# Arduhub_plane.net
KiCad netlist of a schematic drawn in EAGLE
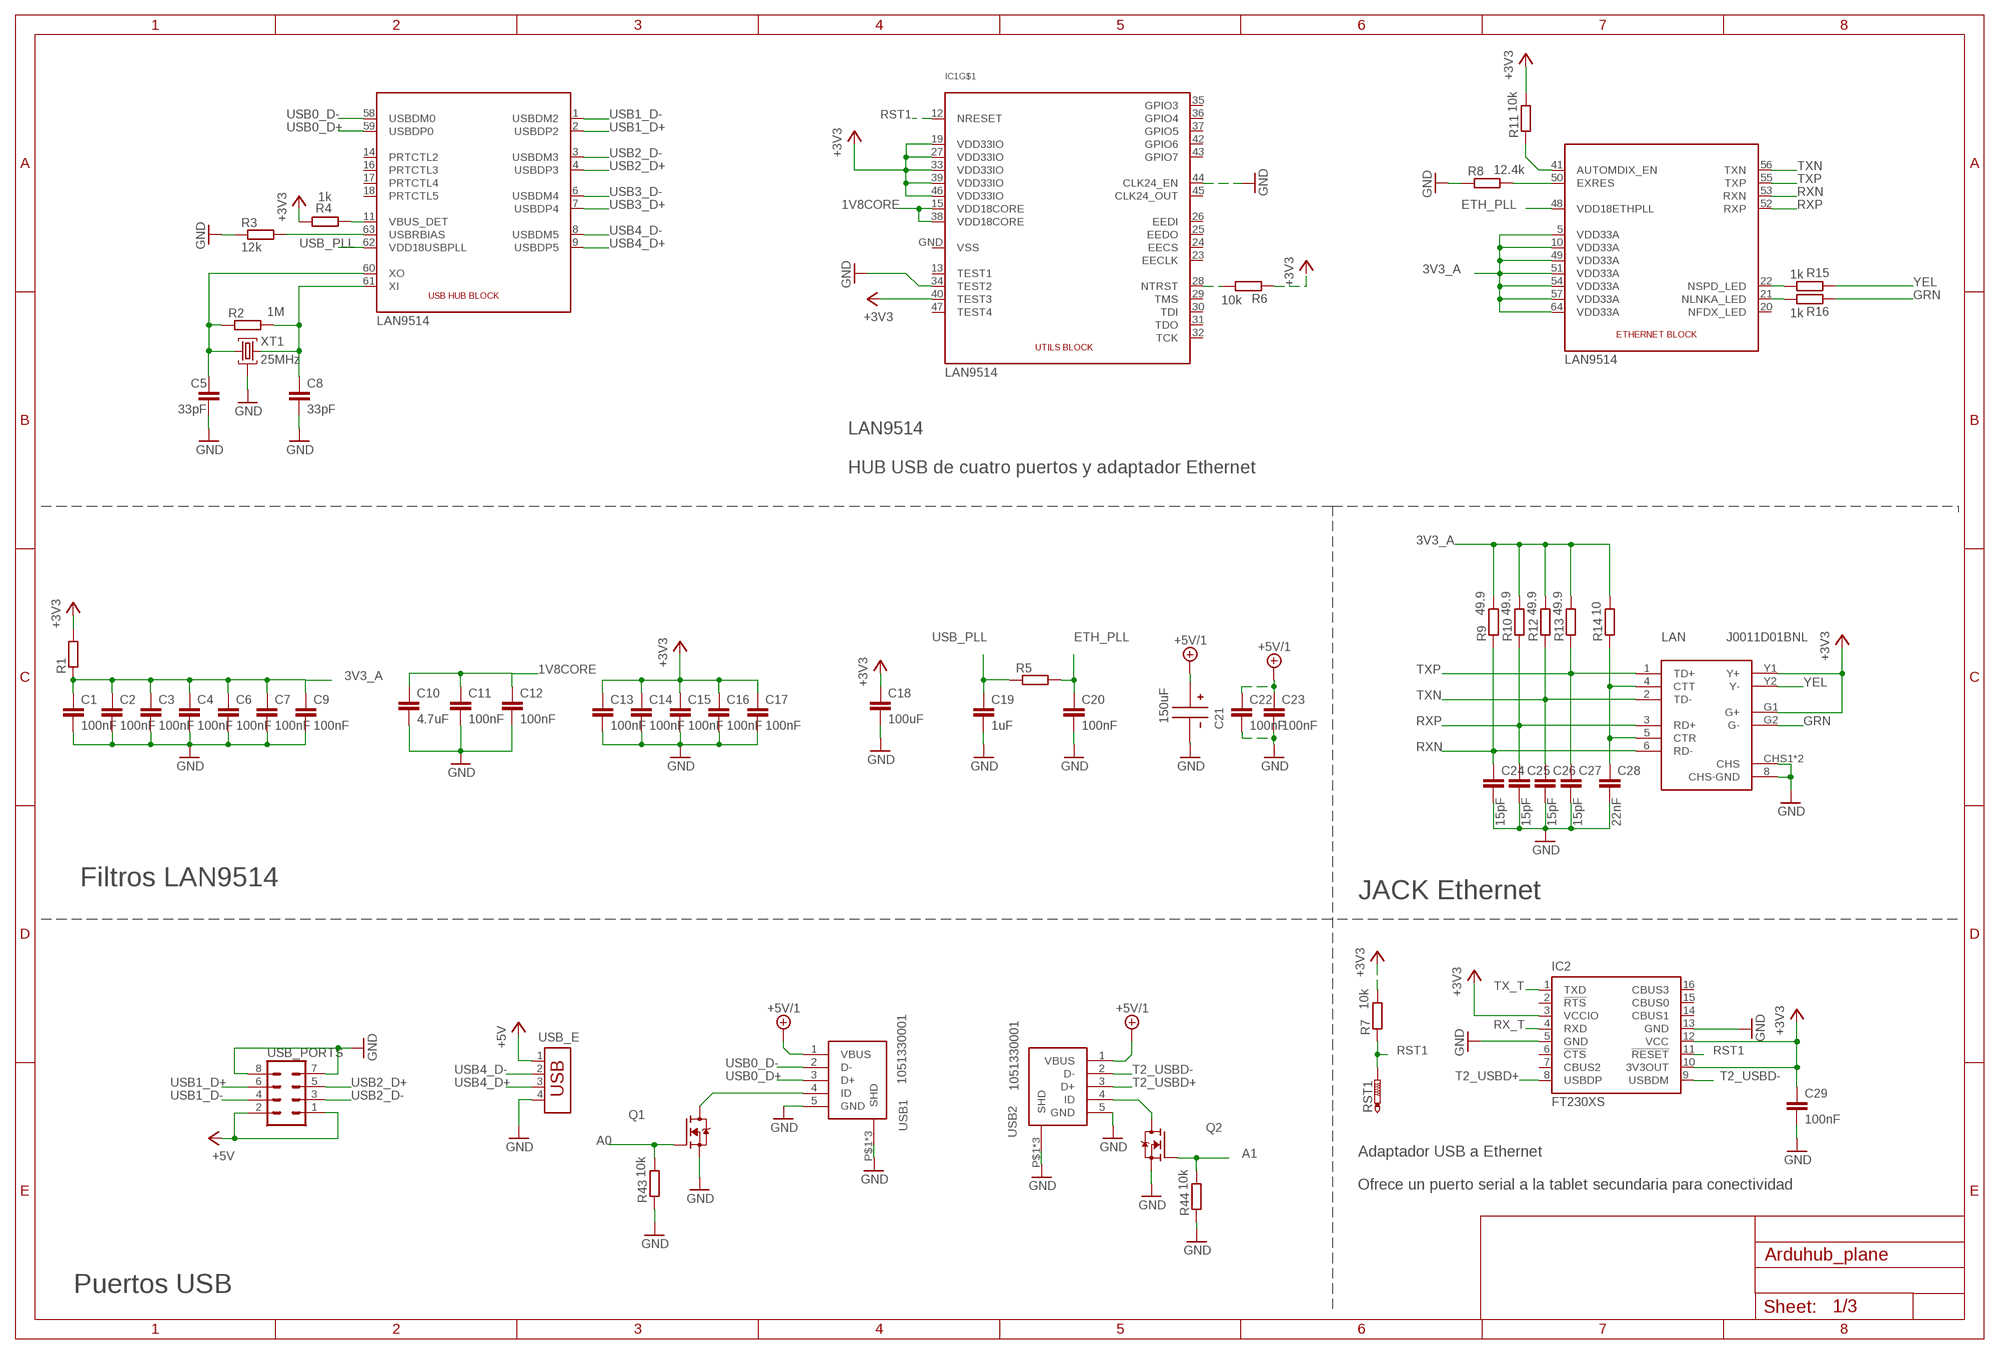
[diagram p0: schematic, sheet 1]
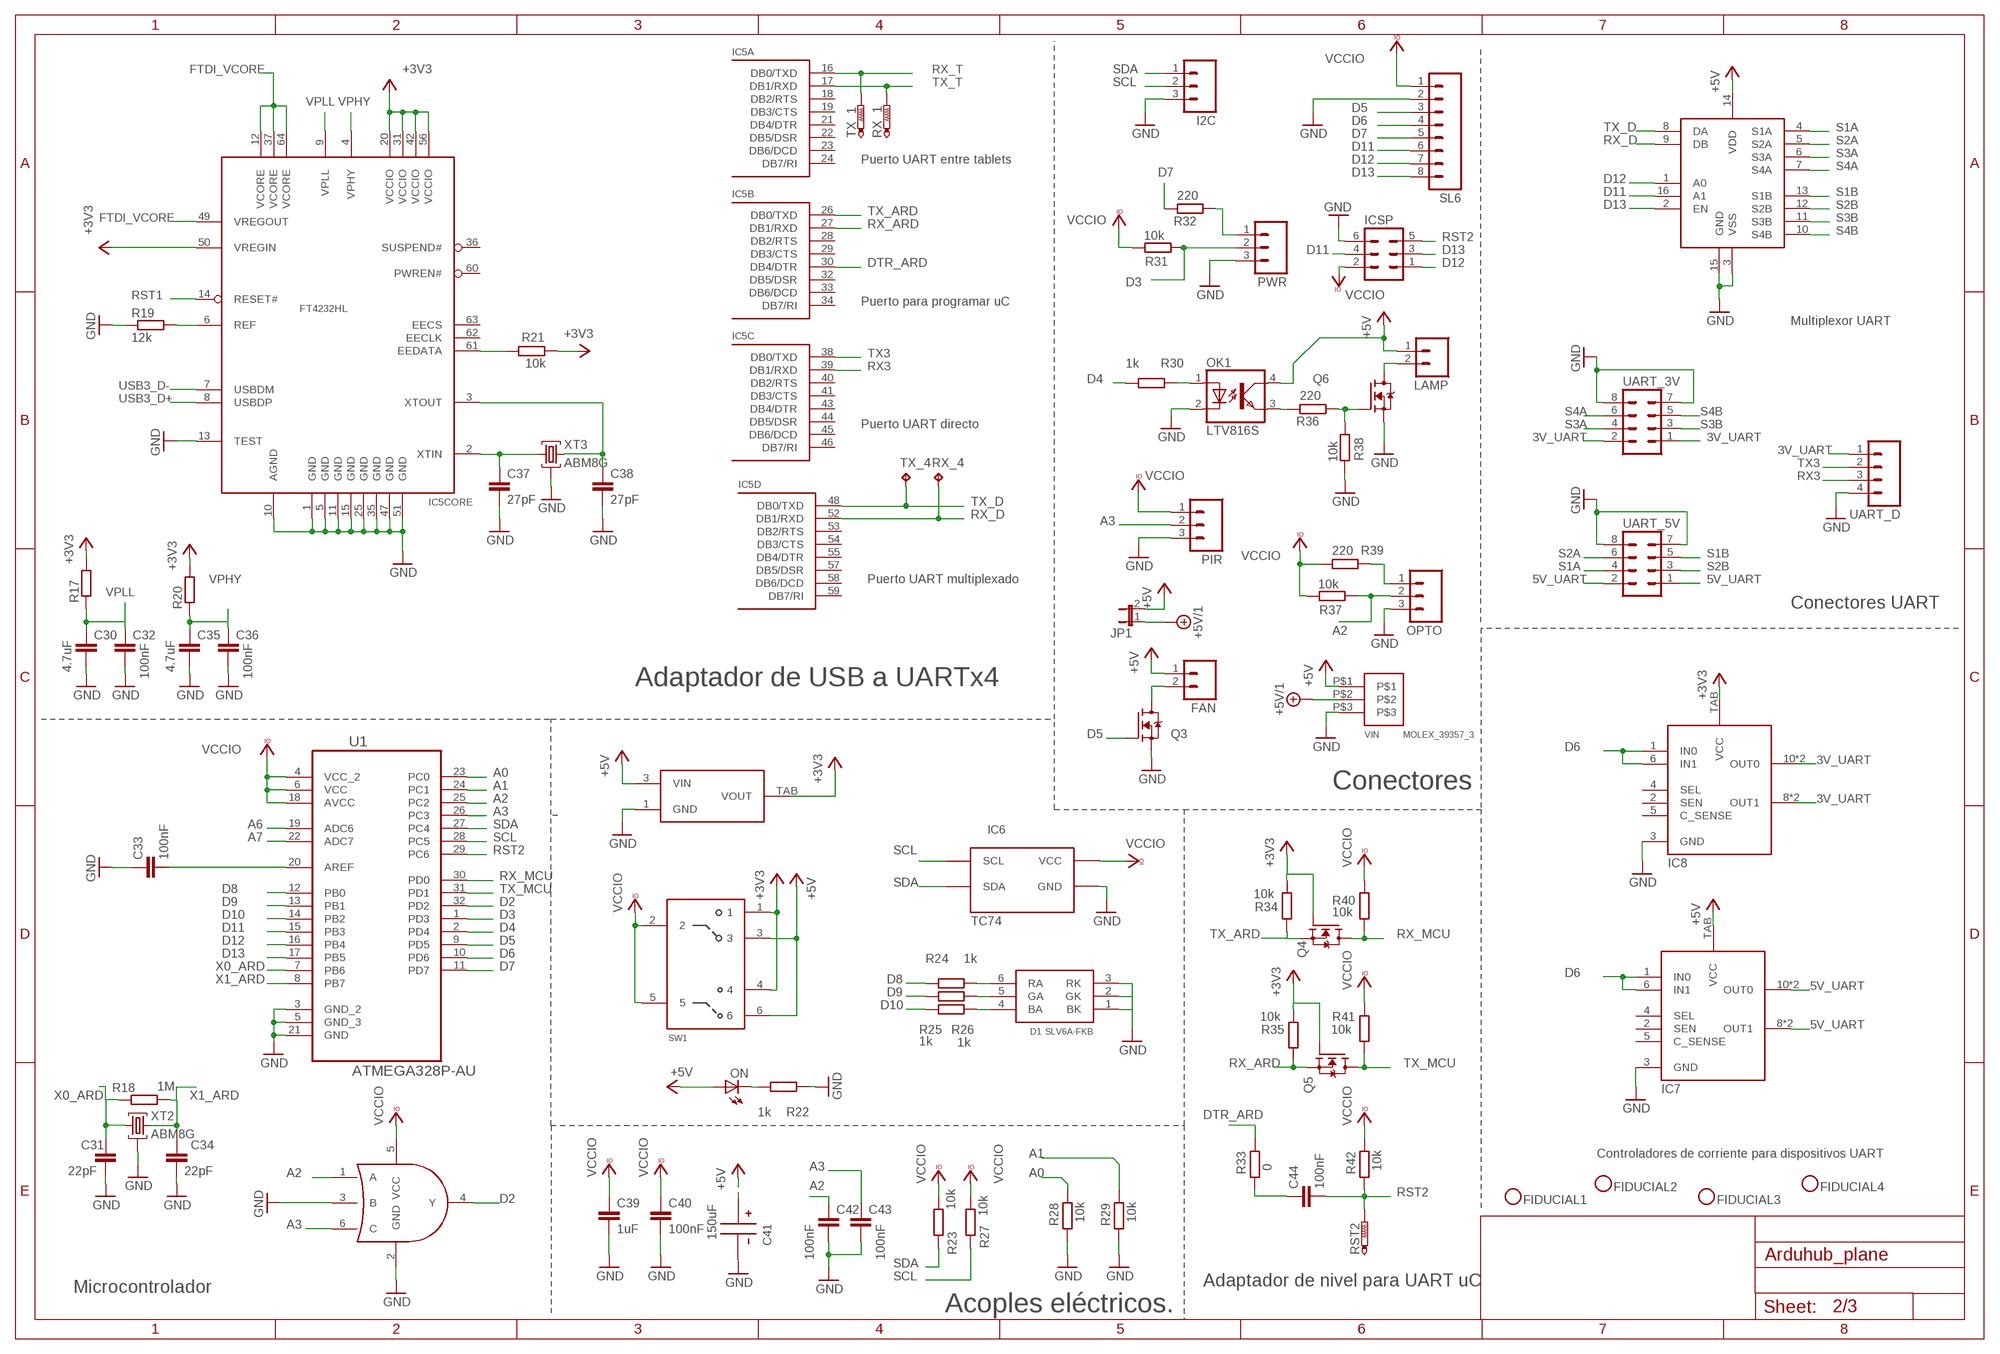
[diagram p1: schematic, sheet 2]
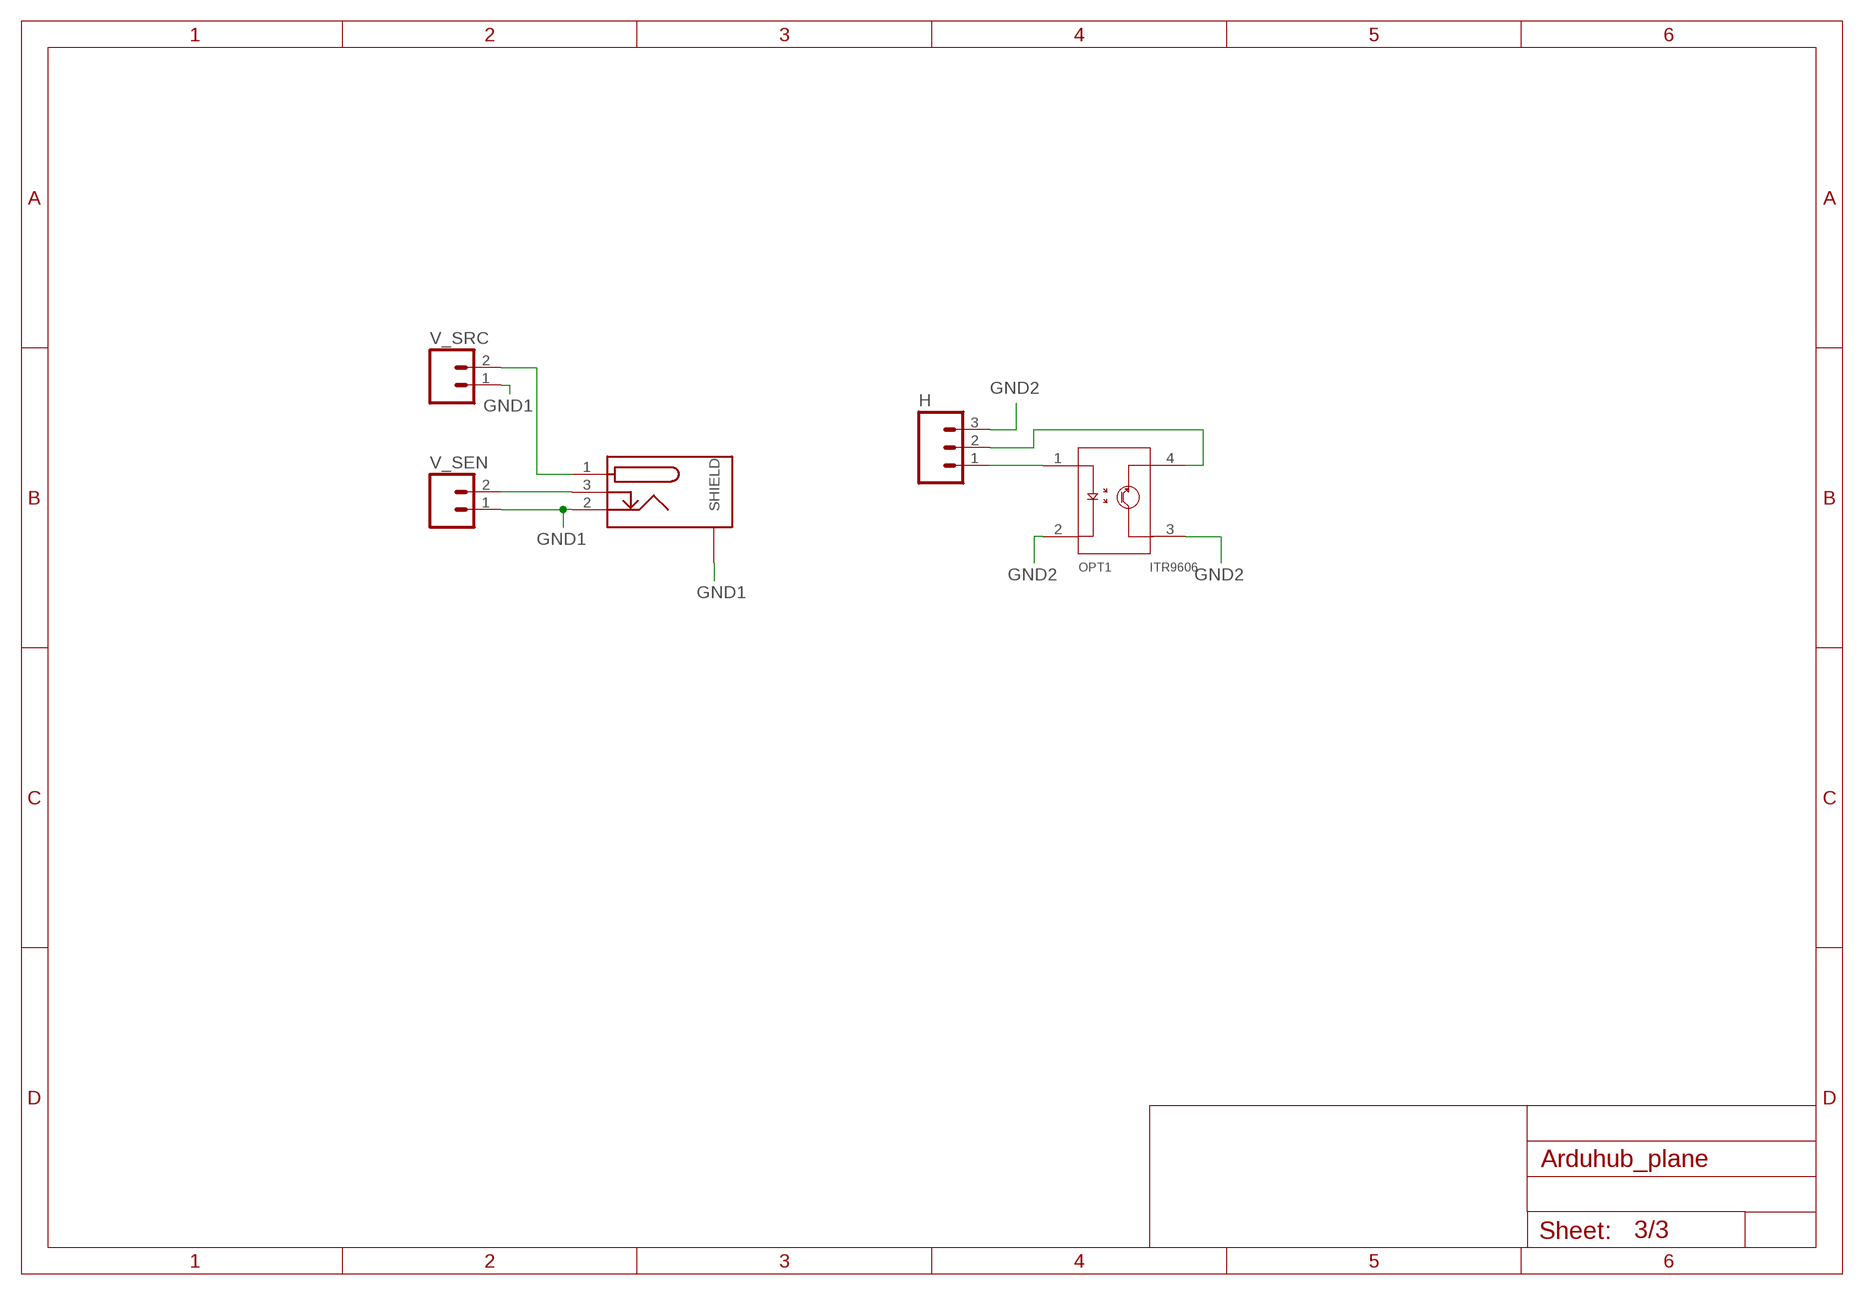
[diagram p2: schematic, sheet 3]

(export (version "E")
  (design (tool "Eeschema 10.0.6"))
  (components
    (comp (ref "C30")
      (value "4.7uF")
      (footprint "eagle-import:C0402")
      (libsource (lib "eagle-import") (part "C-EUC0402"))
    )
    (comp (ref "C31")
      (value "22pF")
      (footprint "eagle-import:C0402")
      (libsource (lib "eagle-import") (part "C-EUC0402"))
    )
    (comp (ref "C32")
      (value "100nF")
      (footprint "eagle-import:C0402")
      (libsource (lib "eagle-import") (part "C-EUC0402"))
    )
    (comp (ref "C33")
      (value "100nF")
      (footprint "eagle-import:C0402")
      (libsource (lib "eagle-import") (part "C-EUC0402"))
    )
    (comp (ref "C34")
      (value "22pF")
      (footprint "eagle-import:C0402")
      (libsource (lib "eagle-import") (part "C-EUC0402"))
    )
    (comp (ref "C35")
      (value "4.7uF")
      (footprint "eagle-import:C0402")
      (libsource (lib "eagle-import") (part "C-EUC0402"))
    )
    (comp (ref "C36")
      (value "100nF")
      (footprint "eagle-import:C0402")
      (libsource (lib "eagle-import") (part "C-EUC0402"))
    )
    (comp (ref "C37")
      (value "27pF")
      (footprint "eagle-import:C0402")
      (libsource (lib "eagle-import") (part "C-EUC0402"))
    )
    (comp (ref "C38")
      (value "27pF")
      (footprint "eagle-import:C0402")
      (libsource (lib "eagle-import") (part "C-EUC0402"))
    )
    (comp (ref "C39")
      (value "1uF")
      (footprint "eagle-import:C0402")
      (libsource (lib "eagle-import") (part "C-EUC0402"))
    )
    (comp (ref "C40")
      (value "100nF")
      (footprint "eagle-import:C0402")
      (libsource (lib "eagle-import") (part "C-EUC0402"))
    )
    (comp (ref "C41")
      (value "150uF")
      (footprint "eagle-import:MVA_CAP_F55")
      (libsource (lib "eagle-import") (part "EMVE100ADA151MF55G"))
    )
    (comp (ref "C42")
      (value "100nF")
      (footprint "eagle-import:C0402")
      (libsource (lib "eagle-import") (part "C-EUC0402"))
    )
    (comp (ref "C43")
      (value "100nF")
      (footprint "eagle-import:C0402")
      (libsource (lib "eagle-import") (part "C-EUC0402"))
    )
    (comp (ref "C44")
      (value "100nF")
      (footprint "eagle-import:C0402")
      (libsource (lib "eagle-import") (part "C-EUC0402"))
    )
    (comp (ref "D1")
      (value "SLV6A-FKB")
      (footprint "eagle-import:PLCC-6")
      (libsource (lib "eagle-import") (part "SLV6A-FKB"))
    )
    (comp (ref "FAN")
      (value "M02")
      (footprint "eagle-import:02P")
      (libsource (lib "eagle-import") (part "M02"))
    )
    (comp (ref "FIDUCIAL1")
      (value "FIDU_2C")
      (footprint "eagle-import:FIDUCIAL_TEST_2C")
      (libsource (lib "eagle-import") (part "FIDU_2C"))
    )
    (comp (ref "FIDUCIAL2")
      (value "FIDU_2C")
      (footprint "eagle-import:FIDUCIAL_TEST_2C")
      (libsource (lib "eagle-import") (part "FIDU_2C"))
    )
    (comp (ref "FIDUCIAL3")
      (value "FIDU_2C")
      (footprint "eagle-import:FIDUCIAL_TEST_2C")
      (libsource (lib "eagle-import") (part "FIDU_2C"))
    )
    (comp (ref "FIDUCIAL4")
      (value "FIDU_2C")
      (footprint "eagle-import:FIDUCIAL_TEST_2C")
      (libsource (lib "eagle-import") (part "FIDU_2C"))
    )
    (comp (ref "I2C")
      (value "M03")
      (footprint "eagle-import:03P")
      (libsource (lib "eagle-import") (part "M03"))
    )
    (comp (ref "IC3")
      (value "SN74LVC1G332DBVR")
      (footprint "eagle-import:SOT-23-6")
      (libsource (lib "eagle-import") (part "SN74LVC1G332DBVR"))
    )
    (comp (ref "IC4")
      (value "AP1084D")
      (footprint "eagle-import:TO_252_3")
      (libsource (lib "eagle-import") (part "AP1084D"))
    )
    (comp (ref "IC5")
      (value "FT4232HL")
      (footprint "eagle-import:LQFP64")
      (fields (field (name "REF") "FT4232HL-REEL"))
      (libsource (lib "eagle-import") (part "FT4232HL"))
    )
    (comp (ref "IC6")
      (value "TC74")
      (footprint "eagle-import:SOT-23-5")
      (libsource (lib "eagle-import") (part "TC74"))
    )
    (comp (ref "IC7")
      (value "VND7140AJ12TR")
      (footprint "eagle-import:POWERSSO-12")
      (libsource (lib "eagle-import") (part "VND7140AJ12TR"))
    )
    (comp (ref "IC8")
      (value "VND7140AJ12TR")
      (footprint "eagle-import:POWERSSO-12")
      (libsource (lib "eagle-import") (part "VND7140AJ12TR"))
    )
    (comp (ref "IC9")
      (value "MUX509IPWR")
      (footprint "eagle-import:TSSOP-16")
      (libsource (lib "eagle-import") (part "MUX509IPWR"))
    )
    (comp (ref "ICSP")
      (value "MA03-2")
      (footprint "eagle-import:MA03-2")
      (libsource (lib "eagle-import") (part "MA03-2"))
    )
    (comp (ref "JP1")
      (value "JP1E")
      (footprint "eagle-import:JP1")
      (libsource (lib "eagle-import") (part "JP1E"))
    )
    (comp (ref "LAMP")
      (value "M02")
      (footprint "eagle-import:02P")
      (libsource (lib "eagle-import") (part "M02"))
    )
    (comp (ref "OK1")
      (value "LTV816S")
      (footprint "eagle-import:SMD4")
      (libsource (lib "eagle-import") (part "LTV816S"))
    )
    (comp (ref "ON")
      (value "LED-0603")
      (footprint "eagle-import:LED-603")
      (libsource (lib "eagle-import") (part "LED-0603"))
    )
    (comp (ref "OPTO")
      (value "M03")
      (footprint "eagle-import:03P")
      (libsource (lib "eagle-import") (part "M03"))
    )
    (comp (ref "PIR")
      (value "M03")
      (footprint "eagle-import:03P")
      (libsource (lib "eagle-import") (part "M03"))
    )
    (comp (ref "PWR")
      (value "M03")
      (footprint "eagle-import:03P")
      (libsource (lib "eagle-import") (part "M03"))
    )
    (comp (ref "Q3")
      (value "TRANSISTOR_FET_BS170-SOT-23")
      (footprint "eagle-import:SOT-23")
      (libsource (lib "eagle-import") (part "TRANSISTOR_FET_BS170-SOT-23"))
    )
    (comp (ref "Q4")
      (value "TRANSISTOR_FET_BS170-SOT-23")
      (footprint "eagle-import:SOT-23")
      (libsource (lib "eagle-import") (part "TRANSISTOR_FET_BS170-SOT-23"))
    )
    (comp (ref "Q5")
      (value "TRANSISTOR_FET_BS170-SOT-23")
      (footprint "eagle-import:SOT-23")
      (libsource (lib "eagle-import") (part "TRANSISTOR_FET_BS170-SOT-23"))
    )
    (comp (ref "Q6")
      (value "TRANSISTOR_FET_BS170-SOT-23")
      (footprint "eagle-import:SOT-23")
      (libsource (lib "eagle-import") (part "TRANSISTOR_FET_BS170-SOT-23"))
    )
    (comp (ref "R17")
      (value "R-EU_R0603")
      (footprint "eagle-import:R0603")
      (libsource (lib "eagle-import") (part "R-EU_R0603"))
    )
    (comp (ref "R18")
      (value "1M")
      (footprint "eagle-import:R0402")
      (libsource (lib "eagle-import") (part "R-EU_R0402"))
    )
    (comp (ref "R19")
      (value "12k")
      (footprint "eagle-import:R0402")
      (libsource (lib "eagle-import") (part "R-EU_R0402"))
    )
    (comp (ref "R20")
      (value "R-EU_R0603")
      (footprint "eagle-import:R0603")
      (libsource (lib "eagle-import") (part "R-EU_R0603"))
    )
    (comp (ref "R21")
      (value "10k")
      (footprint "eagle-import:R0402")
      (libsource (lib "eagle-import") (part "R-EU_R0402"))
    )
    (comp (ref "R22")
      (value "1k")
      (footprint "eagle-import:R0402")
      (libsource (lib "eagle-import") (part "R-EU_R0402"))
    )
    (comp (ref "R23")
      (value "10k")
      (footprint "eagle-import:R0402")
      (libsource (lib "eagle-import") (part "R-EU_R0402"))
    )
    (comp (ref "R24")
      (value "1k")
      (footprint "eagle-import:R0402")
      (libsource (lib "eagle-import") (part "R-EU_R0402"))
    )
    (comp (ref "R25")
      (value "1k")
      (footprint "eagle-import:R0402")
      (libsource (lib "eagle-import") (part "R-EU_R0402"))
    )
    (comp (ref "R26")
      (value "1k")
      (footprint "eagle-import:R0402")
      (libsource (lib "eagle-import") (part "R-EU_R0402"))
    )
    (comp (ref "R27")
      (value "10k")
      (footprint "eagle-import:R0402")
      (libsource (lib "eagle-import") (part "R-EU_R0402"))
    )
    (comp (ref "R28")
      (value "10k")
      (footprint "eagle-import:R0402")
      (libsource (lib "eagle-import") (part "R-EU_R0402"))
    )
    (comp (ref "R29")
      (value "10k")
      (footprint "eagle-import:R0402")
      (libsource (lib "eagle-import") (part "R-EU_R0402"))
    )
    (comp (ref "R30")
      (value "1k")
      (footprint "eagle-import:R0402")
      (libsource (lib "eagle-import") (part "R-EU_R0402"))
    )
    (comp (ref "R31")
      (value "10k")
      (footprint "eagle-import:R0402")
      (libsource (lib "eagle-import") (part "R-EU_R0402"))
    )
    (comp (ref "R32")
      (value "220")
      (footprint "eagle-import:R0402")
      (libsource (lib "eagle-import") (part "R-EU_R0402"))
    )
    (comp (ref "R33")
      (value "0")
      (footprint "eagle-import:R0402")
      (libsource (lib "eagle-import") (part "R-EU_R0402"))
    )
    (comp (ref "R34")
      (value "10k")
      (footprint "eagle-import:R0402")
      (libsource (lib "eagle-import") (part "R-EU_R0402"))
    )
    (comp (ref "R35")
      (value "10k")
      (footprint "eagle-import:R0402")
      (libsource (lib "eagle-import") (part "R-EU_R0402"))
    )
    (comp (ref "R36")
      (value "220")
      (footprint "eagle-import:R0402")
      (libsource (lib "eagle-import") (part "R-EU_R0402"))
    )
    (comp (ref "R37")
      (value "10k")
      (footprint "eagle-import:R0402")
      (libsource (lib "eagle-import") (part "R-EU_R0402"))
    )
    (comp (ref "R38")
      (value "10k")
      (footprint "eagle-import:R0402")
      (libsource (lib "eagle-import") (part "R-EU_R0402"))
    )
    (comp (ref "R39")
      (value "220")
      (footprint "eagle-import:R0402")
      (libsource (lib "eagle-import") (part "R-EU_R0402"))
    )
    (comp (ref "R40")
      (value "10k")
      (footprint "eagle-import:R0402")
      (libsource (lib "eagle-import") (part "R-EU_R0402"))
    )
    (comp (ref "R41")
      (value "10k")
      (footprint "eagle-import:R0402")
      (libsource (lib "eagle-import") (part "R-EU_R0402"))
    )
    (comp (ref "R42")
      (value "10k")
      (footprint "eagle-import:R0402")
      (libsource (lib "eagle-import") (part "R-EU_R0402"))
    )
    (comp (ref "RST2")
      (value "PTR1TP06SQ")
      (footprint "eagle-import:TP06SQ")
      (libsource (lib "eagle-import") (part "PTR1TP06SQ"))
    )
    (comp (ref "RX_1")
      (value "PTR1TP06SQ")
      (footprint "eagle-import:TP06SQ")
      (libsource (lib "eagle-import") (part "PTR1TP06SQ"))
    )
    (comp (ref "RX_4")
      (value "TPTP06SQ")
      (footprint "eagle-import:TP06SQ")
      (libsource (lib "eagle-import") (part "TPTP06SQ"))
    )
    (comp (ref "SL6")
      (value "M08")
      (footprint "eagle-import:08P")
      (libsource (lib "eagle-import") (part "M08"))
    )
    (comp (ref "SW1")
      (value "452403012014")
      (footprint "eagle-import:452403012014")
      (libsource (lib "eagle-import") (part "452403012014"))
    )
    (comp (ref "TX_1")
      (value "PTR1TP06SQ")
      (footprint "eagle-import:TP06SQ")
      (libsource (lib "eagle-import") (part "PTR1TP06SQ"))
    )
    (comp (ref "TX_4")
      (value "TPTP06SQ")
      (footprint "eagle-import:TP06SQ")
      (libsource (lib "eagle-import") (part "TPTP06SQ"))
    )
    (comp (ref "U1")
      (value "ATMEGA328P-AU")
      (footprint "eagle-import:QFP80P900X900X120-32N")
      (libsource (lib "eagle-import") (part "ATMEGA328P-AU"))
    )
    (comp (ref "UART_3V")
      (value "MA04-2")
      (footprint "eagle-import:MA04-2")
      (libsource (lib "eagle-import") (part "MA04-2"))
    )
    (comp (ref "UART_5V")
      (value "MA04-2")
      (footprint "eagle-import:MA04-2")
      (libsource (lib "eagle-import") (part "MA04-2"))
    )
    (comp (ref "UART_D")
      (value "M04")
      (footprint "eagle-import:04P")
      (libsource (lib "eagle-import") (part "M04"))
    )
    (comp (ref "VIN")
      (value "MOLEX_39357_3")
      (footprint "eagle-import:MOLEX_39357-3")
      (libsource (lib "eagle-import") (part "MOLEX_39357_3"))
    )
    (comp (ref "XT2")
      (value "ABM8G")
      (footprint "eagle-import:ABM8G")
      (libsource (lib "eagle-import") (part "ABM8G"))
    )
    (comp (ref "XT3")
      (value "ABM8G")
      (footprint "eagle-import:ABM8G")
      (libsource (lib "eagle-import") (part "ABM8G"))
    )
    (comp (ref "H")
      (value "M03")
      (footprint "eagle-import:03P")
      (libsource (lib "eagle-import") (part "M03"))
    )
    (comp (ref "OPT1")
      (value "ITR9606")
      (footprint "eagle-import:ITR9606")
      (libsource (lib "eagle-import") (part "ITR9606"))
    )
    (comp (ref "PLUG")
      (value "PJ051A")
      (footprint "eagle-import:PJ051A")
      (libsource (lib "eagle-import") (part "PJ051A"))
    )
    (comp (ref "V_SEN")
      (value "M02")
      (footprint "eagle-import:02P")
      (libsource (lib "eagle-import") (part "M02"))
    )
    (comp (ref "V_SRC")
      (value "M02")
      (footprint "eagle-import:02P")
      (libsource (lib "eagle-import") (part "M02"))
    )
    (comp (ref "C1")
      (value "100nF")
      (footprint "eagle-import:C0402")
      (libsource (lib "eagle-import") (part "C-EUC0402"))
    )
    (comp (ref "C2")
      (value "100nF")
      (footprint "eagle-import:C0402")
      (libsource (lib "eagle-import") (part "C-EUC0402"))
    )
    (comp (ref "C3")
      (value "100nF")
      (footprint "eagle-import:C0402")
      (libsource (lib "eagle-import") (part "C-EUC0402"))
    )
    (comp (ref "C4")
      (value "100nF")
      (footprint "eagle-import:C0402")
      (libsource (lib "eagle-import") (part "C-EUC0402"))
    )
    (comp (ref "C5")
      (value "33pF")
      (footprint "eagle-import:C0402")
      (libsource (lib "eagle-import") (part "C-EUC0402"))
    )
    (comp (ref "C6")
      (value "100nF")
      (footprint "eagle-import:C0402")
      (libsource (lib "eagle-import") (part "C-EUC0402"))
    )
    (comp (ref "C7")
      (value "100nF")
      (footprint "eagle-import:C0402")
      (libsource (lib "eagle-import") (part "C-EUC0402"))
    )
    (comp (ref "C8")
      (value "33pF")
      (footprint "eagle-import:C0402")
      (libsource (lib "eagle-import") (part "C-EUC0402"))
    )
    (comp (ref "C9")
      (value "100nF")
      (footprint "eagle-import:C0402")
      (libsource (lib "eagle-import") (part "C-EUC0402"))
    )
    (comp (ref "C10")
      (value "4.7uF")
      (footprint "eagle-import:C0402")
      (libsource (lib "eagle-import") (part "C-EUC0402"))
    )
    (comp (ref "C11")
      (value "100nF")
      (footprint "eagle-import:C0402")
      (libsource (lib "eagle-import") (part "C-EUC0402"))
    )
    (comp (ref "C12")
      (value "100nF")
      (footprint "eagle-import:C0402")
      (libsource (lib "eagle-import") (part "C-EUC0402"))
    )
    (comp (ref "C13")
      (value "100nF")
      (footprint "eagle-import:C0402")
      (libsource (lib "eagle-import") (part "C-EUC0402"))
    )
    (comp (ref "C14")
      (value "100nF")
      (footprint "eagle-import:C0402")
      (libsource (lib "eagle-import") (part "C-EUC0402"))
    )
    (comp (ref "C15")
      (value "100nF")
      (footprint "eagle-import:C0402")
      (libsource (lib "eagle-import") (part "C-EUC0402"))
    )
    (comp (ref "C16")
      (value "100nF")
      (footprint "eagle-import:C0402")
      (libsource (lib "eagle-import") (part "C-EUC0402"))
    )
    (comp (ref "C17")
      (value "100nF")
      (footprint "eagle-import:C0402")
      (libsource (lib "eagle-import") (part "C-EUC0402"))
    )
    (comp (ref "C18")
      (value "100uF")
      (footprint "eagle-import:C0603")
      (libsource (lib "eagle-import") (part "C-EUC0603"))
    )
    (comp (ref "C19")
      (value "1uF")
      (footprint "eagle-import:C0402")
      (libsource (lib "eagle-import") (part "C-EUC0402"))
    )
    (comp (ref "C20")
      (value "100nF")
      (footprint "eagle-import:C0402")
      (libsource (lib "eagle-import") (part "C-EUC0402"))
    )
    (comp (ref "C21")
      (value "150uF")
      (footprint "eagle-import:MVA_CAP_F55")
      (libsource (lib "eagle-import") (part "EMVE100ADA151MF55G"))
    )
    (comp (ref "C22")
      (value "100nF")
      (footprint "eagle-import:C0402")
      (libsource (lib "eagle-import") (part "C-EUC0402"))
    )
    (comp (ref "C23")
      (value "100nF")
      (footprint "eagle-import:C0402")
      (libsource (lib "eagle-import") (part "C-EUC0402"))
    )
    (comp (ref "C24")
      (value "15pF")
      (footprint "eagle-import:C0402")
      (libsource (lib "eagle-import") (part "C-EUC0402"))
    )
    (comp (ref "C25")
      (value "15pF")
      (footprint "eagle-import:C0402")
      (libsource (lib "eagle-import") (part "C-EUC0402"))
    )
    (comp (ref "C26")
      (value "15pF")
      (footprint "eagle-import:C0402")
      (libsource (lib "eagle-import") (part "C-EUC0402"))
    )
    (comp (ref "C27")
      (value "15pF")
      (footprint "eagle-import:C0402")
      (libsource (lib "eagle-import") (part "C-EUC0402"))
    )
    (comp (ref "C28")
      (value "22nF")
      (footprint "eagle-import:C0402")
      (libsource (lib "eagle-import") (part "C-EUC0402"))
    )
    (comp (ref "C29")
      (value "100nF")
      (footprint "eagle-import:C0402")
      (libsource (lib "eagle-import") (part "C-EUC0402"))
    )
    (comp (ref "IC1")
      (value "LAN9514")
      (footprint "eagle-import:QFN64")
      (fields (field (name "REF") "LAN9514-JZX-TR"))
      (libsource (lib "eagle-import") (part "LAN9514"))
    )
    (comp (ref "IC2")
      (value "FT230XS")
      (footprint "eagle-import:SSOP16")
      (libsource (lib "eagle-import") (part "FT230XS"))
    )
    (comp (ref "LAN")
      (value "J0011D01BNL")
      (footprint "eagle-import:J0011D01BNL")
      (libsource (lib "eagle-import") (part "J0011D01BNL"))
    )
    (comp (ref "Q1")
      (value "TRANSISTOR_FET_BS170-SOT-23")
      (footprint "eagle-import:SOT-23")
      (libsource (lib "eagle-import") (part "TRANSISTOR_FET_BS170-SOT-23"))
    )
    (comp (ref "Q2")
      (value "TRANSISTOR_FET_BS170-SOT-23")
      (footprint "eagle-import:SOT-23")
      (libsource (lib "eagle-import") (part "TRANSISTOR_FET_BS170-SOT-23"))
    )
    (comp (ref "R1")
      (value "R-EU_R0603")
      (footprint "eagle-import:R0603")
      (libsource (lib "eagle-import") (part "R-EU_R0603"))
    )
    (comp (ref "R2")
      (value "1M")
      (footprint "eagle-import:R0402")
      (libsource (lib "eagle-import") (part "R-EU_R0402"))
    )
    (comp (ref "R3")
      (value "12k")
      (footprint "eagle-import:R0402")
      (libsource (lib "eagle-import") (part "R-EU_R0402"))
    )
    (comp (ref "R4")
      (value "1k")
      (footprint "eagle-import:R0402")
      (libsource (lib "eagle-import") (part "R-EU_R0402"))
    )
    (comp (ref "R5")
      (value "R-EU_R0603")
      (footprint "eagle-import:R0603")
      (libsource (lib "eagle-import") (part "R-EU_R0603"))
    )
    (comp (ref "R6")
      (value "10k")
      (footprint "eagle-import:R0402")
      (libsource (lib "eagle-import") (part "R-EU_R0402"))
    )
    (comp (ref "R7")
      (value "10k")
      (footprint "eagle-import:R0402")
      (libsource (lib "eagle-import") (part "R-EU_R0402"))
    )
    (comp (ref "R8")
      (value "12.4k")
      (footprint "eagle-import:R0402")
      (libsource (lib "eagle-import") (part "R-EU_R0402"))
    )
    (comp (ref "R9")
      (value "49.9")
      (footprint "eagle-import:R0402")
      (libsource (lib "eagle-import") (part "R-EU_R0402"))
    )
    (comp (ref "R10")
      (value "49.9")
      (footprint "eagle-import:R0402")
      (libsource (lib "eagle-import") (part "R-EU_R0402"))
    )
    (comp (ref "R11")
      (value "10k")
      (footprint "eagle-import:R0402")
      (libsource (lib "eagle-import") (part "R-EU_R0402"))
    )
    (comp (ref "R12")
      (value "49.9")
      (footprint "eagle-import:R0402")
      (libsource (lib "eagle-import") (part "R-EU_R0402"))
    )
    (comp (ref "R13")
      (value "49.9")
      (footprint "eagle-import:R0402")
      (libsource (lib "eagle-import") (part "R-EU_R0402"))
    )
    (comp (ref "R14")
      (value "10")
      (footprint "eagle-import:R0402")
      (libsource (lib "eagle-import") (part "R-EU_R0402"))
    )
    (comp (ref "R15")
      (value "1k")
      (footprint "eagle-import:R0402")
      (libsource (lib "eagle-import") (part "R-EU_R0402"))
    )
    (comp (ref "R16")
      (value "1k")
      (footprint "eagle-import:R0402")
      (libsource (lib "eagle-import") (part "R-EU_R0402"))
    )
    (comp (ref "R43")
      (value "10k")
      (footprint "eagle-import:R0402")
      (libsource (lib "eagle-import") (part "R-EU_R0402"))
    )
    (comp (ref "R44")
      (value "10k")
      (footprint "eagle-import:R0402")
      (libsource (lib "eagle-import") (part "R-EU_R0402"))
    )
    (comp (ref "RST1")
      (value "PTR1B1,27")
      (footprint "eagle-import:B1,27")
      (libsource (lib "eagle-import") (part "PTR1B1,27"))
    )
    (comp (ref "USB1")
      (value "1051330001")
      (footprint "eagle-import:1051330001")
      (libsource (lib "eagle-import") (part "1051330001"))
    )
    (comp (ref "USB2")
      (value "1051330001")
      (footprint "eagle-import:1051330001")
      (libsource (lib "eagle-import") (part "1051330001"))
    )
    (comp (ref "USB_E")
      (value "USB-787616")
      (footprint "eagle-import:USB")
      (libsource (lib "eagle-import") (part "USB-787616"))
    )
    (comp (ref "USB_PORTS")
      (value "MA04-2")
      (footprint "eagle-import:MA04-2")
      (libsource (lib "eagle-import") (part "MA04-2"))
    )
    (comp (ref "XT1")
      (value "25MHz")
      (footprint "eagle-import:ABM8G")
      (libsource (lib "eagle-import") (part "ABM8G"))
    )
  )
  (nets
    (net (code "1") (name "+3V3") (class "Default")
      (node (ref "C13") (pin "1") (pinfunction "1_1") (pintype "passive"))
      (node (ref "C14") (pin "1") (pinfunction "1_1") (pintype "passive"))
      (node (ref "C15") (pin "1") (pinfunction "1_1") (pintype "passive"))
      (node (ref "C16") (pin "1") (pinfunction "1_1") (pintype "passive"))
      (node (ref "C17") (pin "1") (pinfunction "1_1") (pintype "passive"))
      (node (ref "C18") (pin "1") (pinfunction "1_1") (pintype "passive"))
      (node (ref "C29") (pin "1") (pinfunction "1_1") (pintype "passive"))
      (node (ref "IC1") (pin "19") (pinfunction "VDD33IO_19") (pintype "bidirectional"))
      (node (ref "IC1") (pin "27") (pinfunction "VDD33IO_27") (pintype "bidirectional"))
      (node (ref "IC1") (pin "33") (pinfunction "VDD33IO_33") (pintype "bidirectional"))
      (node (ref "IC1") (pin "39") (pinfunction "VDD33IO_39") (pintype "bidirectional"))
      (node (ref "IC1") (pin "40") (pinfunction "TEST3_40") (pintype "bidirectional"))
      (node (ref "IC1") (pin "46") (pinfunction "VDD33IO_46") (pintype "bidirectional"))
      (node (ref "IC2") (pin "10") (pinfunction "3V3OUT_10") (pintype "output"))
      (node (ref "IC2") (pin "12") (pinfunction "VCC_12") (pintype "power_in"))
      (node (ref "IC2") (pin "3") (pinfunction "VCCIO_3") (pintype "power_in"))
      (node (ref "IC4") (pin "TAB") (pinfunction "VOUT_TAB") (pintype "bidirectional"))
      (node (ref "IC5") (pin "20") (pinfunction "VCCIO_20") (pintype "power_in"))
      (node (ref "IC5") (pin "31") (pinfunction "VCCIO_31") (pintype "power_in"))
      (node (ref "IC5") (pin "42") (pinfunction "VCCIO_42") (pintype "power_in"))
      (node (ref "IC5") (pin "50") (pinfunction "VREGIN_50") (pintype "bidirectional"))
      (node (ref "IC5") (pin "56") (pinfunction "VCCIO_56") (pintype "power_in"))
      (node (ref "IC8") (pin "TAB") (pinfunction "VCC_TAB") (pintype "bidirectional"))
      (node (ref "LAN") (pin "G1") (pinfunction "G+_G1") (pintype "bidirectional"))
      (node (ref "LAN") (pin "Y1") (pinfunction "Y+_Y1") (pintype "bidirectional"))
      (node (ref "Q4") (pin "1") (pinfunction "G_1") (pintype "passive"))
      (node (ref "Q5") (pin "1") (pinfunction "G_1") (pintype "passive"))
      (node (ref "R1") (pin "2") (pinfunction "2_2") (pintype "passive"))
      (node (ref "R11") (pin "2") (pinfunction "2_2") (pintype "passive"))
      (node (ref "R17") (pin "2") (pinfunction "2_2") (pintype "passive"))
      (node (ref "R20") (pin "2") (pinfunction "2_2") (pintype "passive"))
      (node (ref "R21") (pin "1") (pinfunction "1_1") (pintype "passive"))
      (node (ref "R34") (pin "1") (pinfunction "1_1") (pintype "passive"))
      (node (ref "R35") (pin "1") (pinfunction "1_1") (pintype "passive"))
      (node (ref "R4") (pin "2") (pinfunction "2_2") (pintype "passive"))
      (node (ref "R6") (pin "1") (pinfunction "1_1") (pintype "passive"))
      (node (ref "R7") (pin "2") (pinfunction "2_2") (pintype "passive"))
      (node (ref "SW1") (pin "1") (pinfunction "1_1") (pintype "bidirectional"))
      (node (ref "SW1") (pin "4") (pinfunction "4_4") (pintype "bidirectional"))
    )
    (net (code "2") (name "+5V") (class "Default")
      (node (ref "C41") (pin "P$+") (pinfunction "P$+_P$+") (pintype "bidirectional"))
      (node (ref "FAN") (pin "1") (pinfunction "1_1") (pintype "passive"))
      (node (ref "IC4") (pin "3") (pinfunction "VIN_3") (pintype "bidirectional"))
      (node (ref "IC7") (pin "TAB") (pinfunction "VCC_TAB") (pintype "bidirectional"))
      (node (ref "IC9") (pin "14") (pinfunction "VDD_14") (pintype "bidirectional"))
      (node (ref "JP1") (pin "2") (pinfunction "2_2") (pintype "passive"))
      (node (ref "LAMP") (pin "1") (pinfunction "1_1") (pintype "passive"))
      (node (ref "OK1") (pin "4") (pinfunction "COL_4") (pintype "passive"))
      (node (ref "ON") (pin "A") (pinfunction "A_A") (pintype "passive"))
      (node (ref "SW1") (pin "3") (pinfunction "3_3") (pintype "bidirectional"))
      (node (ref "SW1") (pin "6") (pinfunction "6_6") (pintype "bidirectional"))
      (node (ref "USB_E") (pin "1") (pinfunction "1_1") (pintype "passive"))
      (node (ref "USB_PORTS") (pin "1") (pinfunction "1_1") (pintype "passive"))
      (node (ref "USB_PORTS") (pin "2") (pinfunction "2_2") (pintype "passive"))
      (node (ref "VIN") (pin "P$1") (pinfunction "P$1_P$1") (pintype "bidirectional"))
    )
    (net (code "3") (name "+5V{slash}1") (class "Default")
      (node (ref "C21") (pin "P$+") (pinfunction "P$+_P$+") (pintype "bidirectional"))
      (node (ref "C22") (pin "1") (pinfunction "1_1") (pintype "passive"))
      (node (ref "C23") (pin "1") (pinfunction "1_1") (pintype "passive"))
      (node (ref "JP1") (pin "1") (pinfunction "1_1") (pintype "passive"))
      (node (ref "USB1") (pin "1") (pinfunction "VBUS_1") (pintype "bidirectional"))
      (node (ref "USB2") (pin "1") (pinfunction "VBUS_1") (pintype "bidirectional"))
      (node (ref "VIN") (pin "P$2") (pinfunction "P$2_P$2") (pintype "bidirectional"))
    )
    (net (code "4") (name "1V8CORE") (class "Default")
      (node (ref "C10") (pin "1") (pinfunction "1_1") (pintype "passive"))
      (node (ref "C11") (pin "1") (pinfunction "1_1") (pintype "passive"))
      (node (ref "C12") (pin "1") (pinfunction "1_1") (pintype "passive"))
      (node (ref "IC1") (pin "15") (pinfunction "VDD18CORE_15") (pintype "bidirectional"))
      (node (ref "IC1") (pin "38") (pinfunction "VDD18CORE_38") (pintype "bidirectional"))
    )
    (net (code "5") (name "3V3_A") (class "Default")
      (node (ref "C1") (pin "1") (pinfunction "1_1") (pintype "passive"))
      (node (ref "C2") (pin "1") (pinfunction "1_1") (pintype "passive"))
      (node (ref "C3") (pin "1") (pinfunction "1_1") (pintype "passive"))
      (node (ref "C4") (pin "1") (pinfunction "1_1") (pintype "passive"))
      (node (ref "C6") (pin "1") (pinfunction "1_1") (pintype "passive"))
      (node (ref "C7") (pin "1") (pinfunction "1_1") (pintype "passive"))
      (node (ref "C9") (pin "1") (pinfunction "1_1") (pintype "passive"))
      (node (ref "IC1") (pin "10") (pinfunction "VDD33A_10") (pintype "bidirectional"))
      (node (ref "IC1") (pin "49") (pinfunction "VDD33A_49") (pintype "bidirectional"))
      (node (ref "IC1") (pin "5") (pinfunction "VDD33A_5") (pintype "bidirectional"))
      (node (ref "IC1") (pin "51") (pinfunction "VDD33A_51") (pintype "bidirectional"))
      (node (ref "IC1") (pin "54") (pinfunction "VDD33A_54") (pintype "bidirectional"))
      (node (ref "IC1") (pin "57") (pinfunction "VDD33A_57") (pintype "bidirectional"))
      (node (ref "IC1") (pin "64") (pinfunction "VDD33A_64") (pintype "bidirectional"))
      (node (ref "R1") (pin "1") (pinfunction "1_1") (pintype "passive"))
      (node (ref "R10") (pin "2") (pinfunction "2_2") (pintype "passive"))
      (node (ref "R12") (pin "2") (pinfunction "2_2") (pintype "passive"))
      (node (ref "R13") (pin "2") (pinfunction "2_2") (pintype "passive"))
      (node (ref "R14") (pin "2") (pinfunction "2_2") (pintype "passive"))
      (node (ref "R9") (pin "2") (pinfunction "2_2") (pintype "passive"))
    )
    (net (code "6") (name "3V_UART") (class "Default")
      (node (ref "IC8") (pin "10") (pinfunction "OUT0_10") (pintype "bidirectional"))
      (node (ref "IC8") (pin "11") (pinfunction "OUT0_11") (pintype "bidirectional"))
      (node (ref "IC8") (pin "8") (pinfunction "OUT1_8") (pintype "bidirectional"))
      (node (ref "IC8") (pin "9") (pinfunction "OUT1_9") (pintype "bidirectional"))
      (node (ref "UART_3V") (pin "1") (pinfunction "1_1") (pintype "passive"))
      (node (ref "UART_3V") (pin "2") (pinfunction "2_2") (pintype "passive"))
      (node (ref "UART_D") (pin "1") (pinfunction "1_1") (pintype "passive"))
    )
    (net (code "7") (name "5V_UART") (class "Default")
      (node (ref "IC7") (pin "10") (pinfunction "OUT0_10") (pintype "bidirectional"))
      (node (ref "IC7") (pin "11") (pinfunction "OUT0_11") (pintype "bidirectional"))
      (node (ref "IC7") (pin "8") (pinfunction "OUT1_8") (pintype "bidirectional"))
      (node (ref "IC7") (pin "9") (pinfunction "OUT1_9") (pintype "bidirectional"))
      (node (ref "UART_5V") (pin "1") (pinfunction "1_1") (pintype "passive"))
      (node (ref "UART_5V") (pin "2") (pinfunction "2_2") (pintype "passive"))
    )
    (net (code "8") (name "A0") (class "Default")
      (node (ref "Q1") (pin "1") (pinfunction "G_1") (pintype "passive"))
      (node (ref "R28") (pin "1") (pinfunction "1_1") (pintype "passive"))
      (node (ref "R43") (pin "2") (pinfunction "2_2") (pintype "passive"))
      (node (ref "U1") (pin "23") (pinfunction "PC0_23") (pintype "bidirectional"))
    )
    (net (code "9") (name "A1") (class "Default")
      (node (ref "Q2") (pin "1") (pinfunction "G_1") (pintype "passive"))
      (node (ref "R29") (pin "1") (pinfunction "1_1") (pintype "passive"))
      (node (ref "R44") (pin "2") (pinfunction "2_2") (pintype "passive"))
      (node (ref "U1") (pin "24") (pinfunction "PC1_24") (pintype "bidirectional"))
    )
    (net (code "10") (name "A2") (class "Default")
      (node (ref "C42") (pin "1") (pinfunction "1_1") (pintype "passive"))
      (node (ref "IC3") (pin "1") (pinfunction "A_1") (pintype "input"))
      (node (ref "OPTO") (pin "2") (pinfunction "2_2") (pintype "passive"))
      (node (ref "R37") (pin "2") (pinfunction "2_2") (pintype "passive"))
      (node (ref "U1") (pin "25") (pinfunction "PC2_25") (pintype "bidirectional"))
    )
    (net (code "11") (name "A3") (class "Default")
      (node (ref "C43") (pin "1") (pinfunction "1_1") (pintype "passive"))
      (node (ref "IC3") (pin "6") (pinfunction "C_6") (pintype "input"))
      (node (ref "PIR") (pin "2") (pinfunction "2_2") (pintype "passive"))
      (node (ref "U1") (pin "26") (pinfunction "PC3_26") (pintype "bidirectional"))
    )
    (net (code "12") (name "A6") (class "Default")
      (node (ref "U1") (pin "19") (pinfunction "ADC6_19") (pintype "input"))
    )
    (net (code "13") (name "A7") (class "Default")
      (node (ref "U1") (pin "22") (pinfunction "ADC7_22") (pintype "input"))
    )
    (net (code "14") (name "D2") (class "Default")
      (node (ref "IC3") (pin "4") (pinfunction "Y_4") (pintype "output"))
      (node (ref "U1") (pin "32") (pinfunction "PD2_32") (pintype "bidirectional"))
    )
    (net (code "15") (name "D3") (class "Default")
      (node (ref "PWR") (pin "2") (pinfunction "2_2") (pintype "passive"))
      (node (ref "R31") (pin "2") (pinfunction "2_2") (pintype "passive"))
      (node (ref "U1") (pin "1") (pinfunction "PD3_1") (pintype "bidirectional"))
    )
    (net (code "16") (name "D4") (class "Default")
      (node (ref "R30") (pin "2") (pinfunction "2_2") (pintype "passive"))
      (node (ref "U1") (pin "2") (pinfunction "PD4_2") (pintype "bidirectional"))
    )
    (net (code "17") (name "D5") (class "Default")
      (node (ref "Q3") (pin "1") (pinfunction "G_1") (pintype "passive"))
      (node (ref "SL6") (pin "3") (pinfunction "3_3") (pintype "passive"))
      (node (ref "U1") (pin "9") (pinfunction "PD5_9") (pintype "bidirectional"))
    )
    (net (code "18") (name "D6") (class "Default")
      (node (ref "IC7") (pin "1") (pinfunction "IN0_1") (pintype "bidirectional"))
      (node (ref "IC7") (pin "6") (pinfunction "IN1_6") (pintype "bidirectional"))
      (node (ref "IC8") (pin "1") (pinfunction "IN0_1") (pintype "bidirectional"))
      (node (ref "IC8") (pin "6") (pinfunction "IN1_6") (pintype "bidirectional"))
      (node (ref "SL6") (pin "4") (pinfunction "4_4") (pintype "passive"))
      (node (ref "U1") (pin "10") (pinfunction "PD6_10") (pintype "bidirectional"))
    )
    (net (code "19") (name "D7") (class "Default")
      (node (ref "R32") (pin "2") (pinfunction "2_2") (pintype "passive"))
      (node (ref "SL6") (pin "5") (pinfunction "5_5") (pintype "passive"))
      (node (ref "U1") (pin "11") (pinfunction "PD7_11") (pintype "bidirectional"))
    )
    (net (code "20") (name "D8") (class "Default")
      (node (ref "R24") (pin "1") (pinfunction "1_1") (pintype "passive"))
      (node (ref "U1") (pin "12") (pinfunction "PB0_12") (pintype "bidirectional"))
    )
    (net (code "21") (name "D9") (class "Default")
      (node (ref "R25") (pin "1") (pinfunction "1_1") (pintype "passive"))
      (node (ref "U1") (pin "13") (pinfunction "PB1_13") (pintype "bidirectional"))
    )
    (net (code "22") (name "D10") (class "Default")
      (node (ref "R26") (pin "1") (pinfunction "1_1") (pintype "passive"))
      (node (ref "U1") (pin "14") (pinfunction "PB2_14") (pintype "bidirectional"))
    )
    (net (code "23") (name "D11") (class "Default")
      (node (ref "IC9") (pin "16") (pinfunction "A1_16") (pintype "bidirectional"))
      (node (ref "ICSP") (pin "4") (pinfunction "4_4") (pintype "passive"))
      (node (ref "SL6") (pin "6") (pinfunction "6_6") (pintype "passive"))
      (node (ref "U1") (pin "15") (pinfunction "PB3_15") (pintype "bidirectional"))
    )
    (net (code "24") (name "D12") (class "Default")
      (node (ref "IC9") (pin "1") (pinfunction "A0_1") (pintype "bidirectional"))
      (node (ref "ICSP") (pin "1") (pinfunction "1_1") (pintype "passive"))
      (node (ref "SL6") (pin "7") (pinfunction "7_7") (pintype "passive"))
      (node (ref "U1") (pin "16") (pinfunction "PB4_16") (pintype "bidirectional"))
    )
    (net (code "25") (name "D13") (class "Default")
      (node (ref "IC9") (pin "2") (pinfunction "EN_2") (pintype "bidirectional"))
      (node (ref "ICSP") (pin "3") (pinfunction "3_3") (pintype "passive"))
      (node (ref "SL6") (pin "8") (pinfunction "8_8") (pintype "passive"))
      (node (ref "U1") (pin "17") (pinfunction "PB5_17") (pintype "bidirectional"))
    )
    (net (code "26") (name "DTR_ARD") (class "Default")
      (node (ref "IC5") (pin "30") (pinfunction "DB4/DTR_30") (pintype "bidirectional"))
      (node (ref "R33") (pin "1") (pinfunction "1_1") (pintype "passive"))
    )
    (net (code "27") (name "ETH_PLL") (class "Default")
      (node (ref "C20") (pin "1") (pinfunction "1_1") (pintype "passive"))
      (node (ref "IC1") (pin "48") (pinfunction "VDD18ETHPLL_48") (pintype "bidirectional"))
      (node (ref "R5") (pin "2") (pinfunction "2_2") (pintype "passive"))
    )
    (net (code "28") (name "FTDI_VCORE") (class "Default")
      (node (ref "IC5") (pin "12") (pinfunction "VCORE_12") (pintype "power_in"))
      (node (ref "IC5") (pin "37") (pinfunction "VCORE_37") (pintype "power_in"))
      (node (ref "IC5") (pin "49") (pinfunction "VREGOUT_49") (pintype "output"))
      (node (ref "IC5") (pin "64") (pinfunction "VCORE_64") (pintype "power_in"))
    )
    (net (code "29") (name "GND") (class "Default")
      (node (ref "C1") (pin "2") (pinfunction "2_2") (pintype "passive"))
      (node (ref "C10") (pin "2") (pinfunction "2_2") (pintype "passive"))
      (node (ref "C11") (pin "2") (pinfunction "2_2") (pintype "passive"))
      (node (ref "C12") (pin "2") (pinfunction "2_2") (pintype "passive"))
      (node (ref "C13") (pin "2") (pinfunction "2_2") (pintype "passive"))
      (node (ref "C14") (pin "2") (pinfunction "2_2") (pintype "passive"))
      (node (ref "C15") (pin "2") (pinfunction "2_2") (pintype "passive"))
      (node (ref "C16") (pin "2") (pinfunction "2_2") (pintype "passive"))
      (node (ref "C17") (pin "2") (pinfunction "2_2") (pintype "passive"))
      (node (ref "C18") (pin "2") (pinfunction "2_2") (pintype "passive"))
      (node (ref "C19") (pin "2") (pinfunction "2_2") (pintype "passive"))
      (node (ref "C2") (pin "2") (pinfunction "2_2") (pintype "passive"))
      (node (ref "C20") (pin "2") (pinfunction "2_2") (pintype "passive"))
      (node (ref "C21") (pin "P$-") (pinfunction "P$-_P$-") (pintype "bidirectional"))
      (node (ref "C22") (pin "2") (pinfunction "2_2") (pintype "passive"))
      (node (ref "C23") (pin "2") (pinfunction "2_2") (pintype "passive"))
      (node (ref "C24") (pin "2") (pinfunction "2_2") (pintype "passive"))
      (node (ref "C25") (pin "2") (pinfunction "2_2") (pintype "passive"))
      (node (ref "C26") (pin "2") (pinfunction "2_2") (pintype "passive"))
      (node (ref "C27") (pin "2") (pinfunction "2_2") (pintype "passive"))
      (node (ref "C28") (pin "2") (pinfunction "2_2") (pintype "passive"))
      (node (ref "C29") (pin "2") (pinfunction "2_2") (pintype "passive"))
      (node (ref "C3") (pin "2") (pinfunction "2_2") (pintype "passive"))
      (node (ref "C30") (pin "2") (pinfunction "2_2") (pintype "passive"))
      (node (ref "C31") (pin "2") (pinfunction "2_2") (pintype "passive"))
      (node (ref "C32") (pin "2") (pinfunction "2_2") (pintype "passive"))
      (node (ref "C33") (pin "1") (pinfunction "1_1") (pintype "passive"))
      (node (ref "C34") (pin "2") (pinfunction "2_2") (pintype "passive"))
      (node (ref "C35") (pin "2") (pinfunction "2_2") (pintype "passive"))
      (node (ref "C36") (pin "2") (pinfunction "2_2") (pintype "passive"))
      (node (ref "C37") (pin "2") (pinfunction "2_2") (pintype "passive"))
      (node (ref "C38") (pin "2") (pinfunction "2_2") (pintype "passive"))
      (node (ref "C39") (pin "2") (pinfunction "2_2") (pintype "passive"))
      (node (ref "C4") (pin "2") (pinfunction "2_2") (pintype "passive"))
      (node (ref "C40") (pin "2") (pinfunction "2_2") (pintype "passive"))
      (node (ref "C41") (pin "P$-") (pinfunction "P$-_P$-") (pintype "bidirectional"))
      (node (ref "C42") (pin "2") (pinfunction "2_2") (pintype "passive"))
      (node (ref "C43") (pin "2") (pinfunction "2_2") (pintype "passive"))
      (node (ref "C5") (pin "2") (pinfunction "2_2") (pintype "passive"))
      (node (ref "C6") (pin "2") (pinfunction "2_2") (pintype "passive"))
      (node (ref "C7") (pin "2") (pinfunction "2_2") (pintype "passive"))
      (node (ref "C8") (pin "2") (pinfunction "2_2") (pintype "passive"))
      (node (ref "C9") (pin "2") (pinfunction "2_2") (pintype "passive"))
      (node (ref "D1") (pin "1") (pinfunction "BK_1") (pintype "bidirectional"))
      (node (ref "D1") (pin "2") (pinfunction "GK_2") (pintype "bidirectional"))
      (node (ref "D1") (pin "3") (pinfunction "RK_3") (pintype "bidirectional"))
      (node (ref "I2C") (pin "3") (pinfunction "3_3") (pintype "passive"))
      (node (ref "IC1") (pin "34") (pinfunction "TEST2_34") (pintype "bidirectional"))
      (node (ref "IC1") (pin "44") (pinfunction "CLK24_EN_44") (pintype "bidirectional"))
      (node (ref "IC2") (pin "13") (pinfunction "GND_13") (pintype "power_in"))
      (node (ref "IC2") (pin "5") (pinfunction "GND_5") (pintype "power_in"))
      (node (ref "IC3") (pin "2") (pinfunction "GND_2") (pintype "power_in"))
      (node (ref "IC3") (pin "3") (pinfunction "B_3") (pintype "input"))
      (node (ref "IC4") (pin "1") (pinfunction "GND_1") (pintype "bidirectional"))
      (node (ref "IC5") (pin "1") (pinfunction "GND_1") (pintype "power_in"))
      (node (ref "IC5") (pin "10") (pinfunction "AGND_10") (pintype "power_in"))
      (node (ref "IC5") (pin "11") (pinfunction "GND_11") (pintype "power_in"))
      (node (ref "IC5") (pin "13") (pinfunction "TEST_13") (pintype "input"))
      (node (ref "IC5") (pin "15") (pinfunction "GND_15") (pintype "power_in"))
      (node (ref "IC5") (pin "25") (pinfunction "GND_25") (pintype "power_in"))
      (node (ref "IC5") (pin "35") (pinfunction "GND_35") (pintype "power_in"))
      (node (ref "IC5") (pin "47") (pinfunction "GND_47") (pintype "power_in"))
      (node (ref "IC5") (pin "5") (pinfunction "GND_5") (pintype "power_in"))
      (node (ref "IC5") (pin "51") (pinfunction "GND_51") (pintype "power_in"))
      (node (ref "IC6") (pin "2") (pinfunction "GND_2") (pintype "bidirectional"))
      (node (ref "IC7") (pin "3") (pinfunction "GND_3") (pintype "bidirectional"))
      (node (ref "IC8") (pin "3") (pinfunction "GND_3") (pintype "bidirectional"))
      (node (ref "IC9") (pin "15") (pinfunction "GND_15") (pintype "bidirectional"))
      (node (ref "IC9") (pin "3") (pinfunction "VSS_3") (pintype "bidirectional"))
      (node (ref "ICSP") (pin "6") (pinfunction "6_6") (pintype "passive"))
      (node (ref "LAN") (pin "8") (pinfunction "CHS-GND_8") (pintype "bidirectional"))
      (node (ref "LAN") (pin "CHS1") (pinfunction "CHS_CHS1") (pintype "bidirectional"))
      (node (ref "LAN") (pin "CHS2") (pinfunction "CHS_CHS2") (pintype "bidirectional"))
      (node (ref "OK1") (pin "2") (pinfunction "C_2") (pintype "passive"))
      (node (ref "OPTO") (pin "3") (pinfunction "3_3") (pintype "passive"))
      (node (ref "PIR") (pin "3") (pinfunction "3_3") (pintype "passive"))
      (node (ref "PWR") (pin "3") (pinfunction "3_3") (pintype "passive"))
      (node (ref "Q1") (pin "2") (pinfunction "S_2") (pintype "passive"))
      (node (ref "Q2") (pin "2") (pinfunction "S_2") (pintype "passive"))
      (node (ref "Q3") (pin "2") (pinfunction "S_2") (pintype "passive"))
      (node (ref "Q6") (pin "2") (pinfunction "S_2") (pintype "passive"))
      (node (ref "R19") (pin "1") (pinfunction "1_1") (pintype "passive"))
      (node (ref "R22") (pin "1") (pinfunction "1_1") (pintype "passive"))
      (node (ref "R28") (pin "2") (pinfunction "2_2") (pintype "passive"))
      (node (ref "R29") (pin "2") (pinfunction "2_2") (pintype "passive"))
      (node (ref "R3") (pin "1") (pinfunction "1_1") (pintype "passive"))
      (node (ref "R38") (pin "1") (pinfunction "1_1") (pintype "passive"))
      (node (ref "R43") (pin "1") (pinfunction "1_1") (pintype "passive"))
      (node (ref "R44") (pin "1") (pinfunction "1_1") (pintype "passive"))
      (node (ref "R8") (pin "1") (pinfunction "1_1") (pintype "passive"))
      (node (ref "SL6") (pin "2") (pinfunction "2_2") (pintype "passive"))
      (node (ref "U1") (pin "21") (pinfunction "GND_21") (pintype "passive"))
      (node (ref "U1") (pin "3") (pinfunction "GND_2_3") (pintype "passive"))
      (node (ref "U1") (pin "5") (pinfunction "GND_3_5") (pintype "passive"))
      (node (ref "UART_3V") (pin "7") (pinfunction "7_7") (pintype "passive"))
      (node (ref "UART_3V") (pin "8") (pinfunction "8_8") (pintype "passive"))
      (node (ref "UART_5V") (pin "7") (pinfunction "7_7") (pintype "passive"))
      (node (ref "UART_5V") (pin "8") (pinfunction "8_8") (pintype "passive"))
      (node (ref "UART_D") (pin "4") (pinfunction "4_4") (pintype "passive"))
      (node (ref "USB1") (pin "5") (pinfunction "GND_5") (pintype "bidirectional"))
      (node (ref "USB1") (pin "P$1") (pinfunction "SHD_P$1") (pintype "bidirectional"))
      (node (ref "USB1") (pin "P$2") (pinfunction "SHD_P$2") (pintype "bidirectional"))
      (node (ref "USB1") (pin "P$3") (pinfunction "SHD_P$3") (pintype "bidirectional"))
      (node (ref "USB2") (pin "5") (pinfunction "GND_5") (pintype "bidirectional"))
      (node (ref "USB2") (pin "P$1") (pinfunction "SHD_P$1") (pintype "bidirectional"))
      (node (ref "USB2") (pin "P$2") (pinfunction "SHD_P$2") (pintype "bidirectional"))
      (node (ref "USB2") (pin "P$3") (pinfunction "SHD_P$3") (pintype "bidirectional"))
      (node (ref "USB_E") (pin "4") (pinfunction "4_4") (pintype "passive"))
      (node (ref "USB_PORTS") (pin "7") (pinfunction "7_7") (pintype "passive"))
      (node (ref "USB_PORTS") (pin "8") (pinfunction "8_8") (pintype "passive"))
      (node (ref "VIN") (pin "P$3") (pinfunction "P$3_P$3") (pintype "bidirectional"))
      (node (ref "XT1") (pin "2") (pinfunction "2_2") (pintype "passive"))
      (node (ref "XT1") (pin "4") (pinfunction "2_4") (pintype "passive"))
      (node (ref "XT2") (pin "2") (pinfunction "2_2") (pintype "passive"))
      (node (ref "XT2") (pin "4") (pinfunction "2_4") (pintype "passive"))
      (node (ref "XT3") (pin "2") (pinfunction "2_2") (pintype "passive"))
      (node (ref "XT3") (pin "4") (pinfunction "2_4") (pintype "passive"))
    )
    (net (code "30") (name "GND1") (class "Default")
      (node (ref "PLUG") (pin "2") (pinfunction "2_2") (pintype "bidirectional"))
      (node (ref "PLUG") (pin "P$1") (pinfunction "SHIELD_P$1") (pintype "bidirectional"))
      (node (ref "PLUG") (pin "P$2") (pinfunction "SHIELD_P$2") (pintype "bidirectional"))
      (node (ref "V_SEN") (pin "1") (pinfunction "1_1") (pintype "passive"))
      (node (ref "V_SRC") (pin "1") (pinfunction "1_1") (pintype "passive"))
    )
    (net (code "31") (name "GND2") (class "Default")
      (node (ref "H") (pin "3") (pinfunction "3_3") (pintype "passive"))
      (node (ref "OPT1") (pin "2") (pinfunction "P$2_2") (pintype "bidirectional"))
      (node (ref "OPT1") (pin "3") (pinfunction "P$3_3") (pintype "bidirectional"))
    )
    (net (code "32") (name "GRN") (class "Default")
      (node (ref "LAN") (pin "G2") (pinfunction "G-_G2") (pintype "bidirectional"))
      (node (ref "R16") (pin "1") (pinfunction "1_1") (pintype "passive"))
    )
    (net (code "33") (name "Net-(C44-Pad1)") (class "Default")
      (node (ref "C44") (pin "1") (pinfunction "1_1") (pintype "passive"))
      (node (ref "R33") (pin "2") (pinfunction "2_2") (pintype "passive"))
    )
    (net (code "34") (name "Net-(D1-BA)") (class "Default")
      (node (ref "D1") (pin "4") (pinfunction "BA_4") (pintype "bidirectional"))
      (node (ref "R26") (pin "2") (pinfunction "2_2") (pintype "passive"))
    )
    (net (code "35") (name "Net-(D1-GA)") (class "Default")
      (node (ref "D1") (pin "5") (pinfunction "GA_5") (pintype "bidirectional"))
      (node (ref "R25") (pin "2") (pinfunction "2_2") (pintype "passive"))
    )
    (net (code "36") (name "Net-(D1-RA)") (class "Default")
      (node (ref "D1") (pin "6") (pinfunction "RA_6") (pintype "bidirectional"))
      (node (ref "R24") (pin "2") (pinfunction "2_2") (pintype "passive"))
    )
    (net (code "37") (name "Net-(IC1A-NTRST)") (class "Default")
      (node (ref "IC1") (pin "28") (pinfunction "NTRST_28") (pintype "bidirectional"))
      (node (ref "R6") (pin "2") (pinfunction "2_2") (pintype "passive"))
    )
    (net (code "38") (name "Net-(IC1B-USBRBIAS)") (class "Default")
      (node (ref "IC1") (pin "63") (pinfunction "USBRBIAS_63") (pintype "bidirectional"))
      (node (ref "R3") (pin "2") (pinfunction "2_2") (pintype "passive"))
    )
    (net (code "39") (name "Net-(IC1B-VBUS_DET)") (class "Default")
      (node (ref "IC1") (pin "11") (pinfunction "VBUS_DET_11") (pintype "bidirectional"))
      (node (ref "R4") (pin "1") (pinfunction "1_1") (pintype "passive"))
    )
    (net (code "40") (name "Net-(IC1B-XI)") (class "Default")
      (node (ref "C8") (pin "1") (pinfunction "1_1") (pintype "passive"))
      (node (ref "IC1") (pin "61") (pinfunction "XI_61") (pintype "bidirectional"))
      (node (ref "R2") (pin "2") (pinfunction "2_2") (pintype "passive"))
      (node (ref "XT1") (pin "3") (pinfunction "3_3") (pintype "passive"))
    )
    (net (code "41") (name "Net-(IC1B-XO)") (class "Default")
      (node (ref "C5") (pin "1") (pinfunction "1_1") (pintype "passive"))
      (node (ref "IC1") (pin "60") (pinfunction "XO_60") (pintype "bidirectional"))
      (node (ref "R2") (pin "1") (pinfunction "1_1") (pintype "passive"))
      (node (ref "XT1") (pin "1") (pinfunction "1_1") (pintype "passive"))
    )
    (net (code "42") (name "Net-(IC1C-AUTOMDIX_EN)") (class "Default")
      (node (ref "IC1") (pin "41") (pinfunction "AUTOMDIX_EN_41") (pintype "bidirectional"))
      (node (ref "R11") (pin "1") (pinfunction "1_1") (pintype "passive"))
    )
    (net (code "43") (name "Net-(IC1C-EXRES)") (class "Default")
      (node (ref "IC1") (pin "50") (pinfunction "EXRES_50") (pintype "bidirectional"))
      (node (ref "R8") (pin "2") (pinfunction "2_2") (pintype "passive"))
    )
    (net (code "44") (name "Net-(IC1C-NLNKA_LED)") (class "Default")
      (node (ref "IC1") (pin "21") (pinfunction "NLNKA_LED_21") (pintype "bidirectional"))
      (node (ref "R16") (pin "2") (pinfunction "2_2") (pintype "passive"))
    )
    (net (code "45") (name "Net-(IC1C-NSPD_LED)") (class "Default")
      (node (ref "IC1") (pin "22") (pinfunction "NSPD_LED_22") (pintype "bidirectional"))
      (node (ref "R15") (pin "2") (pinfunction "2_2") (pintype "passive"))
    )
    (net (code "46") (name "Net-(IC5D-EEDATA)") (class "Default")
      (node (ref "IC5") (pin "61") (pinfunction "EEDATA_61") (pintype "bidirectional"))
      (node (ref "R21") (pin "2") (pinfunction "2_2") (pintype "passive"))
    )
    (net (code "47") (name "Net-(IC5D-REF)") (class "Default")
      (node (ref "IC5") (pin "6") (pinfunction "REF_6") (pintype "input"))
      (node (ref "R19") (pin "2") (pinfunction "2_2") (pintype "passive"))
    )
    (net (code "48") (name "Net-(IC5D-XTIN)") (class "Default")
      (node (ref "C37") (pin "1") (pinfunction "1_1") (pintype "passive"))
      (node (ref "IC5") (pin "2") (pinfunction "XTIN_2") (pintype "input"))
      (node (ref "XT3") (pin "1") (pinfunction "1_1") (pintype "passive"))
    )
    (net (code "49") (name "Net-(IC5D-XTOUT)") (class "Default")
      (node (ref "C38") (pin "1") (pinfunction "1_1") (pintype "passive"))
      (node (ref "IC5") (pin "3") (pinfunction "XTOUT_3") (pintype "output"))
      (node (ref "XT3") (pin "3") (pinfunction "3_3") (pintype "passive"))
    )
    (net (code "50") (name "Net-(LAN-CTR)") (class "Default")
      (node (ref "C28") (pin "1") (pinfunction "1_1") (pintype "passive"))
      (node (ref "LAN") (pin "4") (pinfunction "CTT_4") (pintype "bidirectional"))
      (node (ref "LAN") (pin "5") (pinfunction "CTR_5") (pintype "bidirectional"))
      (node (ref "R14") (pin "1") (pinfunction "1_1") (pintype "passive"))
    )
    (net (code "51") (name "Net-(OK1-A)") (class "Default")
      (node (ref "OK1") (pin "1") (pinfunction "A_1") (pintype "passive"))
      (node (ref "R30") (pin "1") (pinfunction "1_1") (pintype "passive"))
    )
    (net (code "52") (name "Net-(OK1-EMIT)") (class "Default")
      (node (ref "OK1") (pin "3") (pinfunction "EMIT_3") (pintype "passive"))
      (node (ref "R36") (pin "2") (pinfunction "2_2") (pintype "passive"))
    )
    (net (code "53") (name "Net-(ON-PadC)") (class "Default")
      (node (ref "ON") (pin "C") (pinfunction "C_C") (pintype "passive"))
      (node (ref "R22") (pin "2") (pinfunction "2_2") (pintype "passive"))
    )
    (net (code "54") (name "Net-(OPT1-P$1)") (class "Default")
      (node (ref "H") (pin "1") (pinfunction "1_1") (pintype "passive"))
      (node (ref "OPT1") (pin "1") (pinfunction "P$1_1") (pintype "bidirectional"))
    )
    (net (code "55") (name "Net-(OPT1-P$4)") (class "Default")
      (node (ref "H") (pin "2") (pinfunction "2_2") (pintype "passive"))
      (node (ref "OPT1") (pin "4") (pinfunction "P$4_4") (pintype "bidirectional"))
    )
    (net (code "56") (name "Net-(OPTO-Pad1)") (class "Default")
      (node (ref "OPTO") (pin "1") (pinfunction "1_1") (pintype "passive"))
      (node (ref "R39") (pin "1") (pinfunction "1_1") (pintype "passive"))
    )
    (net (code "57") (name "Net-(PLUG-Pad1)") (class "Default")
      (node (ref "PLUG") (pin "1") (pinfunction "1_1") (pintype "bidirectional"))
      (node (ref "V_SRC") (pin "2") (pinfunction "2_2") (pintype "passive"))
    )
    (net (code "58") (name "Net-(PLUG-Pad3)") (class "Default")
      (node (ref "PLUG") (pin "3") (pinfunction "3_3") (pintype "bidirectional"))
      (node (ref "V_SEN") (pin "2") (pinfunction "2_2") (pintype "passive"))
    )
    (net (code "59") (name "Net-(PWR-Pad1)") (class "Default")
      (node (ref "PWR") (pin "1") (pinfunction "1_1") (pintype "passive"))
      (node (ref "R32") (pin "1") (pinfunction "1_1") (pintype "passive"))
    )
    (net (code "60") (name "Net-(Q1-D)") (class "Default")
      (node (ref "Q1") (pin "3") (pinfunction "D_3") (pintype "passive"))
      (node (ref "USB1") (pin "4") (pinfunction "ID_4") (pintype "bidirectional"))
    )
    (net (code "61") (name "Net-(Q2-D)") (class "Default")
      (node (ref "Q2") (pin "3") (pinfunction "D_3") (pintype "passive"))
      (node (ref "USB2") (pin "4") (pinfunction "ID_4") (pintype "bidirectional"))
    )
    (net (code "62") (name "Net-(Q3-D)") (class "Default")
      (node (ref "FAN") (pin "2") (pinfunction "2_2") (pintype "passive"))
      (node (ref "Q3") (pin "3") (pinfunction "D_3") (pintype "passive"))
    )
    (net (code "63") (name "Net-(Q6-D)") (class "Default")
      (node (ref "LAMP") (pin "2") (pinfunction "2_2") (pintype "passive"))
      (node (ref "Q6") (pin "3") (pinfunction "D_3") (pintype "passive"))
    )
    (net (code "64") (name "Net-(Q6-G)") (class "Default")
      (node (ref "Q6") (pin "1") (pinfunction "G_1") (pintype "passive"))
      (node (ref "R36") (pin "1") (pinfunction "1_1") (pintype "passive"))
      (node (ref "R38") (pin "2") (pinfunction "2_2") (pintype "passive"))
    )
    (net (code "65") (name "Net-(U1-AREF)") (class "Default")
      (node (ref "C33") (pin "2") (pinfunction "2_2") (pintype "passive"))
      (node (ref "U1") (pin "20") (pinfunction "AREF_20") (pintype "input"))
    )
    (net (code "66") (name "RST1") (class "Default")
      (node (ref "IC1") (pin "12") (pinfunction "NRESET_12") (pintype "bidirectional"))
      (node (ref "IC2") (pin "11") (pinfunction "~{RESET}_11") (pintype "input"))
      (node (ref "IC5") (pin "14") (pinfunction "RESET#_14") (pintype "input"))
      (node (ref "R7") (pin "1") (pinfunction "1_1") (pintype "passive"))
      (node (ref "RST1") (pin "TP") (pinfunction "TP_TP") (pintype "input"))
    )
    (net (code "67") (name "RST2") (class "Default")
      (node (ref "C44") (pin "2") (pinfunction "2_2") (pintype "passive"))
      (node (ref "ICSP") (pin "5") (pinfunction "5_5") (pintype "passive"))
      (node (ref "R42") (pin "2") (pinfunction "2_2") (pintype "passive"))
      (node (ref "RST2") (pin "TP") (pinfunction "TP_TP") (pintype "input"))
      (node (ref "U1") (pin "29") (pinfunction "PC6_29") (pintype "bidirectional"))
    )
    (net (code "68") (name "RX3") (class "Default")
      (node (ref "IC5") (pin "39") (pinfunction "DB1/RXD_39") (pintype "bidirectional"))
      (node (ref "UART_D") (pin "3") (pinfunction "3_3") (pintype "passive"))
    )
    (net (code "69") (name "RXN") (class "Default")
      (node (ref "C24") (pin "1") (pinfunction "1_1") (pintype "passive"))
      (node (ref "IC1") (pin "53") (pinfunction "RXN_53") (pintype "bidirectional"))
      (node (ref "LAN") (pin "6") (pinfunction "RD-_6") (pintype "bidirectional"))
      (node (ref "R9") (pin "1") (pinfunction "1_1") (pintype "passive"))
    )
    (net (code "70") (name "RXP") (class "Default")
      (node (ref "C25") (pin "1") (pinfunction "1_1") (pintype "passive"))
      (node (ref "IC1") (pin "52") (pinfunction "RXP_52") (pintype "bidirectional"))
      (node (ref "LAN") (pin "3") (pinfunction "RD+_3") (pintype "bidirectional"))
      (node (ref "R10") (pin "1") (pinfunction "1_1") (pintype "passive"))
    )
    (net (code "71") (name "RX_ARD") (class "Default")
      (node (ref "IC5") (pin "27") (pinfunction "DB1/RXD_27") (pintype "bidirectional"))
      (node (ref "Q5") (pin "2") (pinfunction "S_2") (pintype "passive"))
      (node (ref "R35") (pin "2") (pinfunction "2_2") (pintype "passive"))
    )
    (net (code "72") (name "RX_D") (class "Default")
      (node (ref "IC5") (pin "52") (pinfunction "DB1/RXD_52") (pintype "bidirectional"))
      (node (ref "IC9") (pin "9") (pinfunction "DB_9") (pintype "bidirectional"))
      (node (ref "RX_4") (pin "TP") (pinfunction "TP_TP") (pintype "input"))
    )
    (net (code "73") (name "RX_MCU") (class "Default")
      (node (ref "Q4") (pin "3") (pinfunction "D_3") (pintype "passive"))
      (node (ref "R40") (pin "2") (pinfunction "2_2") (pintype "passive"))
      (node (ref "U1") (pin "30") (pinfunction "PD0_30") (pintype "bidirectional"))
    )
    (net (code "74") (name "RX_T") (class "Default")
      (node (ref "IC2") (pin "4") (pinfunction "RXD_4") (pintype "input"))
      (node (ref "IC5") (pin "16") (pinfunction "DB0/TXD_16") (pintype "bidirectional"))
      (node (ref "TX_1") (pin "TP") (pinfunction "TP_TP") (pintype "input"))
    )
    (net (code "75") (name "S1A") (class "Default")
      (node (ref "IC9") (pin "4") (pinfunction "S1A_4") (pintype "bidirectional"))
      (node (ref "UART_5V") (pin "4") (pinfunction "4_4") (pintype "passive"))
    )
    (net (code "76") (name "S1B") (class "Default")
      (node (ref "IC9") (pin "13") (pinfunction "S1B_13") (pintype "bidirectional"))
      (node (ref "UART_5V") (pin "5") (pinfunction "5_5") (pintype "passive"))
    )
    (net (code "77") (name "S2A") (class "Default")
      (node (ref "IC9") (pin "5") (pinfunction "S2A_5") (pintype "bidirectional"))
      (node (ref "UART_5V") (pin "6") (pinfunction "6_6") (pintype "passive"))
    )
    (net (code "78") (name "S2B") (class "Default")
      (node (ref "IC9") (pin "12") (pinfunction "S2B_12") (pintype "bidirectional"))
      (node (ref "UART_5V") (pin "3") (pinfunction "3_3") (pintype "passive"))
    )
    (net (code "79") (name "S3A") (class "Default")
      (node (ref "IC9") (pin "6") (pinfunction "S3A_6") (pintype "bidirectional"))
      (node (ref "UART_3V") (pin "4") (pinfunction "4_4") (pintype "passive"))
    )
    (net (code "80") (name "S3B") (class "Default")
      (node (ref "IC9") (pin "11") (pinfunction "S3B_11") (pintype "bidirectional"))
      (node (ref "UART_3V") (pin "3") (pinfunction "3_3") (pintype "passive"))
    )
    (net (code "81") (name "S4A") (class "Default")
      (node (ref "IC9") (pin "7") (pinfunction "S4A_7") (pintype "bidirectional"))
      (node (ref "UART_3V") (pin "6") (pinfunction "6_6") (pintype "passive"))
    )
    (net (code "82") (name "S4B") (class "Default")
      (node (ref "IC9") (pin "10") (pinfunction "S4B_10") (pintype "bidirectional"))
      (node (ref "UART_3V") (pin "5") (pinfunction "5_5") (pintype "passive"))
    )
    (net (code "83") (name "SCL") (class "Default")
      (node (ref "I2C") (pin "2") (pinfunction "2_2") (pintype "passive"))
      (node (ref "IC6") (pin "4") (pinfunction "SCL_4") (pintype "bidirectional"))
      (node (ref "R27") (pin "2") (pinfunction "2_2") (pintype "passive"))
      (node (ref "U1") (pin "28") (pinfunction "PC5_28") (pintype "bidirectional"))
    )
    (net (code "84") (name "SDA") (class "Default")
      (node (ref "I2C") (pin "1") (pinfunction "1_1") (pintype "passive"))
      (node (ref "IC6") (pin "5") (pinfunction "SDA_5") (pintype "bidirectional"))
      (node (ref "R23") (pin "2") (pinfunction "2_2") (pintype "passive"))
      (node (ref "U1") (pin "27") (pinfunction "PC4_27") (pintype "bidirectional"))
    )
    (net (code "85") (name "T2_USBD+") (class "Default")
      (node (ref "IC2") (pin "8") (pinfunction "USBDP_8") (pintype "input"))
      (node (ref "USB2") (pin "3") (pinfunction "D+_3") (pintype "bidirectional"))
    )
    (net (code "86") (name "T2_USBD-") (class "Default")
      (node (ref "IC2") (pin "9") (pinfunction "USBDM_9") (pintype "input"))
      (node (ref "USB2") (pin "2") (pinfunction "D-_2") (pintype "bidirectional"))
    )
    (net (code "87") (name "TX3") (class "Default")
      (node (ref "IC5") (pin "38") (pinfunction "DB0/TXD_38") (pintype "bidirectional"))
      (node (ref "UART_D") (pin "2") (pinfunction "2_2") (pintype "passive"))
    )
    (net (code "88") (name "TXN") (class "Default")
      (node (ref "C26") (pin "1") (pinfunction "1_1") (pintype "passive"))
      (node (ref "IC1") (pin "56") (pinfunction "TXN_56") (pintype "bidirectional"))
      (node (ref "LAN") (pin "2") (pinfunction "TD-_2") (pintype "bidirectional"))
      (node (ref "R12") (pin "1") (pinfunction "1_1") (pintype "passive"))
    )
    (net (code "89") (name "TXP") (class "Default")
      (node (ref "C27") (pin "1") (pinfunction "1_1") (pintype "passive"))
      (node (ref "IC1") (pin "55") (pinfunction "TXP_55") (pintype "bidirectional"))
      (node (ref "LAN") (pin "1") (pinfunction "TD+_1") (pintype "bidirectional"))
      (node (ref "R13") (pin "1") (pinfunction "1_1") (pintype "passive"))
    )
    (net (code "90") (name "TX_ARD") (class "Default")
      (node (ref "IC5") (pin "26") (pinfunction "DB0/TXD_26") (pintype "bidirectional"))
      (node (ref "Q4") (pin "2") (pinfunction "S_2") (pintype "passive"))
      (node (ref "R34") (pin "2") (pinfunction "2_2") (pintype "passive"))
    )
    (net (code "91") (name "TX_D") (class "Default")
      (node (ref "IC5") (pin "48") (pinfunction "DB0/TXD_48") (pintype "bidirectional"))
      (node (ref "IC9") (pin "8") (pinfunction "DA_8") (pintype "bidirectional"))
      (node (ref "TX_4") (pin "TP") (pinfunction "TP_TP") (pintype "input"))
    )
    (net (code "92") (name "TX_MCU") (class "Default")
      (node (ref "Q5") (pin "3") (pinfunction "D_3") (pintype "passive"))
      (node (ref "R41") (pin "2") (pinfunction "2_2") (pintype "passive"))
      (node (ref "U1") (pin "31") (pinfunction "PD1_31") (pintype "bidirectional"))
    )
    (net (code "93") (name "TX_T") (class "Default")
      (node (ref "IC2") (pin "1") (pinfunction "TXD_1") (pintype "output"))
      (node (ref "IC5") (pin "17") (pinfunction "DB1/RXD_17") (pintype "bidirectional"))
      (node (ref "RX_1") (pin "TP") (pinfunction "TP_TP") (pintype "input"))
    )
    (net (code "94") (name "USB0_D+") (class "Default")
      (node (ref "IC1") (pin "59") (pinfunction "USBDP0_59") (pintype "bidirectional"))
      (node (ref "USB1") (pin "3") (pinfunction "D+_3") (pintype "bidirectional"))
    )
    (net (code "95") (name "USB0_D-") (class "Default")
      (node (ref "IC1") (pin "58") (pinfunction "USBDM0_58") (pintype "bidirectional"))
      (node (ref "USB1") (pin "2") (pinfunction "D-_2") (pintype "bidirectional"))
    )
    (net (code "96") (name "USB1_D+") (class "Default")
      (node (ref "IC1") (pin "2") (pinfunction "USBDP2_2") (pintype "bidirectional"))
      (node (ref "USB_PORTS") (pin "6") (pinfunction "6_6") (pintype "passive"))
    )
    (net (code "97") (name "USB1_D-") (class "Default")
      (node (ref "IC1") (pin "1") (pinfunction "USBDM2_1") (pintype "bidirectional"))
      (node (ref "USB_PORTS") (pin "4") (pinfunction "4_4") (pintype "passive"))
    )
    (net (code "98") (name "USB2_D+") (class "Default")
      (node (ref "IC1") (pin "4") (pinfunction "USBDP3_4") (pintype "bidirectional"))
      (node (ref "USB_PORTS") (pin "5") (pinfunction "5_5") (pintype "passive"))
    )
    (net (code "99") (name "USB2_D-") (class "Default")
      (node (ref "IC1") (pin "3") (pinfunction "USBDM3_3") (pintype "bidirectional"))
      (node (ref "USB_PORTS") (pin "3") (pinfunction "3_3") (pintype "passive"))
    )
    (net (code "100") (name "USB3_D+") (class "Default")
      (node (ref "IC1") (pin "7") (pinfunction "USBDP4_7") (pintype "bidirectional"))
      (node (ref "IC5") (pin "8") (pinfunction "USBDP_8") (pintype "input"))
    )
    (net (code "101") (name "USB3_D-") (class "Default")
      (node (ref "IC1") (pin "6") (pinfunction "USBDM4_6") (pintype "bidirectional"))
      (node (ref "IC5") (pin "7") (pinfunction "USBDM_7") (pintype "input"))
    )
    (net (code "102") (name "USB4_D+") (class "Default")
      (node (ref "IC1") (pin "9") (pinfunction "USBDP5_9") (pintype "bidirectional"))
      (node (ref "USB_E") (pin "3") (pinfunction "3_3") (pintype "passive"))
    )
    (net (code "103") (name "USB4_D-") (class "Default")
      (node (ref "IC1") (pin "8") (pinfunction "USBDM5_8") (pintype "bidirectional"))
      (node (ref "USB_E") (pin "2") (pinfunction "2_2") (pintype "passive"))
    )
    (net (code "104") (name "USB_PLL") (class "Default")
      (node (ref "C19") (pin "1") (pinfunction "1_1") (pintype "passive"))
      (node (ref "IC1") (pin "62") (pinfunction "VDD18USBPLL_62") (pintype "bidirectional"))
      (node (ref "R5") (pin "1") (pinfunction "1_1") (pintype "passive"))
    )
    (net (code "105") (name "VCCIO") (class "Default")
      (node (ref "C39") (pin "1") (pinfunction "1_1") (pintype "passive"))
      (node (ref "C40") (pin "1") (pinfunction "1_1") (pintype "passive"))
      (node (ref "IC3") (pin "5") (pinfunction "VCC_5") (pintype "power_in"))
      (node (ref "IC6") (pin "3") (pinfunction "VCC_3") (pintype "bidirectional"))
      (node (ref "ICSP") (pin "2") (pinfunction "2_2") (pintype "passive"))
      (node (ref "PIR") (pin "1") (pinfunction "1_1") (pintype "passive"))
      (node (ref "R23") (pin "1") (pinfunction "1_1") (pintype "passive"))
      (node (ref "R27") (pin "1") (pinfunction "1_1") (pintype "passive"))
      (node (ref "R31") (pin "1") (pinfunction "1_1") (pintype "passive"))
      (node (ref "R37") (pin "1") (pinfunction "1_1") (pintype "passive"))
      (node (ref "R39") (pin "2") (pinfunction "2_2") (pintype "passive"))
      (node (ref "R40") (pin "1") (pinfunction "1_1") (pintype "passive"))
      (node (ref "R41") (pin "1") (pinfunction "1_1") (pintype "passive"))
      (node (ref "R42") (pin "1") (pinfunction "1_1") (pintype "passive"))
      (node (ref "SL6") (pin "1") (pinfunction "1_1") (pintype "passive"))
      (node (ref "SW1") (pin "2") (pinfunction "2_2") (pintype "bidirectional"))
      (node (ref "SW1") (pin "5") (pinfunction "5_5") (pintype "bidirectional"))
      (node (ref "U1") (pin "18") (pinfunction "AVCC_18") (pintype "power_in"))
      (node (ref "U1") (pin "4") (pinfunction "VCC_2_4") (pintype "power_in"))
      (node (ref "U1") (pin "6") (pinfunction "VCC_6") (pintype "power_in"))
    )
    (net (code "106") (name "VPHY") (class "Default")
      (node (ref "C35") (pin "1") (pinfunction "1_1") (pintype "passive"))
      (node (ref "C36") (pin "1") (pinfunction "1_1") (pintype "passive"))
      (node (ref "IC5") (pin "4") (pinfunction "VPHY_4") (pintype "power_in"))
      (node (ref "R20") (pin "1") (pinfunction "1_1") (pintype "passive"))
    )
    (net (code "107") (name "VPLL") (class "Default")
      (node (ref "C30") (pin "1") (pinfunction "1_1") (pintype "passive"))
      (node (ref "C32") (pin "1") (pinfunction "1_1") (pintype "passive"))
      (node (ref "IC5") (pin "9") (pinfunction "VPLL_9") (pintype "power_in"))
      (node (ref "R17") (pin "1") (pinfunction "1_1") (pintype "passive"))
    )
    (net (code "108") (name "X0_ARD") (class "Default")
      (node (ref "C31") (pin "1") (pinfunction "1_1") (pintype "passive"))
      (node (ref "R18") (pin "1") (pinfunction "1_1") (pintype "passive"))
      (node (ref "U1") (pin "7") (pinfunction "PB6_7") (pintype "bidirectional"))
      (node (ref "XT2") (pin "1") (pinfunction "1_1") (pintype "passive"))
    )
    (net (code "109") (name "X1_ARD") (class "Default")
      (node (ref "C34") (pin "1") (pinfunction "1_1") (pintype "passive"))
      (node (ref "R18") (pin "2") (pinfunction "2_2") (pintype "passive"))
      (node (ref "U1") (pin "8") (pinfunction "PB7_8") (pintype "bidirectional"))
      (node (ref "XT2") (pin "3") (pinfunction "3_3") (pintype "passive"))
    )
    (net (code "110") (name "YEL") (class "Default")
      (node (ref "LAN") (pin "Y2") (pinfunction "Y-_Y2") (pintype "bidirectional"))
      (node (ref "R15") (pin "1") (pinfunction "1_1") (pintype "passive"))
    )
    (net (code "111") (name "unconnected-(IC1A-CLK24_OUT-Pad45)") (class "Default")
      (node (ref "IC1") (pin "45") (pinfunction "CLK24_OUT_45") (pintype "bidirectional"))
    )
    (net (code "112") (name "unconnected-(IC1A-EECLK-Pad23)") (class "Default")
      (node (ref "IC1") (pin "23") (pinfunction "EECLK_23") (pintype "bidirectional"))
    )
    (net (code "113") (name "unconnected-(IC1A-EECS-Pad24)") (class "Default")
      (node (ref "IC1") (pin "24") (pinfunction "EECS_24") (pintype "bidirectional"))
    )
    (net (code "114") (name "unconnected-(IC1A-EEDI-Pad26)") (class "Default")
      (node (ref "IC1") (pin "26") (pinfunction "EEDI_26") (pintype "bidirectional"))
    )
    (net (code "115") (name "unconnected-(IC1A-EEDO-Pad25)") (class "Default")
      (node (ref "IC1") (pin "25") (pinfunction "EEDO_25") (pintype "bidirectional"))
    )
    (net (code "116") (name "unconnected-(IC1A-GPIO3-Pad35)") (class "Default")
      (node (ref "IC1") (pin "35") (pinfunction "GPIO3_35") (pintype "bidirectional"))
    )
    (net (code "117") (name "unconnected-(IC1A-GPIO4-Pad36)") (class "Default")
      (node (ref "IC1") (pin "36") (pinfunction "GPIO4_36") (pintype "bidirectional"))
    )
    (net (code "118") (name "unconnected-(IC1A-GPIO5-Pad37)") (class "Default")
      (node (ref "IC1") (pin "37") (pinfunction "GPIO5_37") (pintype "bidirectional"))
    )
    (net (code "119") (name "unconnected-(IC1A-GPIO6-Pad42)") (class "Default")
      (node (ref "IC1") (pin "42") (pinfunction "GPIO6_42") (pintype "bidirectional"))
    )
    (net (code "120") (name "unconnected-(IC1A-GPIO7-Pad43)") (class "Default")
      (node (ref "IC1") (pin "43") (pinfunction "GPIO7_43") (pintype "bidirectional"))
    )
    (net (code "121") (name "unconnected-(IC1A-TCK-Pad32)") (class "Default")
      (node (ref "IC1") (pin "32") (pinfunction "TCK_32") (pintype "bidirectional"))
    )
    (net (code "122") (name "unconnected-(IC1A-TDI-Pad30)") (class "Default")
      (node (ref "IC1") (pin "30") (pinfunction "TDI_30") (pintype "bidirectional"))
    )
    (net (code "123") (name "unconnected-(IC1A-TDO-Pad31)") (class "Default")
      (node (ref "IC1") (pin "31") (pinfunction "TDO_31") (pintype "bidirectional"))
    )
    (net (code "124") (name "unconnected-(IC1A-TEST1-Pad13)") (class "Default")
      (node (ref "IC1") (pin "13") (pinfunction "TEST1_13") (pintype "bidirectional"))
    )
    (net (code "125") (name "unconnected-(IC1A-TEST4-Pad47)") (class "Default")
      (node (ref "IC1") (pin "47") (pinfunction "TEST4_47") (pintype "bidirectional"))
    )
    (net (code "126") (name "unconnected-(IC1A-TMS-Pad29)") (class "Default")
      (node (ref "IC1") (pin "29") (pinfunction "TMS_29") (pintype "bidirectional"))
    )
    (net (code "127") (name "unconnected-(IC1A-VSS-PadGND)") (class "Default")
      (node (ref "IC1") (pin "GND") (pinfunction "VSS_GND") (pintype "bidirectional"))
    )
    (net (code "128") (name "unconnected-(IC1B-PRTCTL2-Pad14)") (class "Default")
      (node (ref "IC1") (pin "14") (pinfunction "PRTCTL2_14") (pintype "bidirectional"))
    )
    (net (code "129") (name "unconnected-(IC1B-PRTCTL3-Pad16)") (class "Default")
      (node (ref "IC1") (pin "16") (pinfunction "PRTCTL3_16") (pintype "bidirectional"))
    )
    (net (code "130") (name "unconnected-(IC1B-PRTCTL4-Pad17)") (class "Default")
      (node (ref "IC1") (pin "17") (pinfunction "PRTCTL4_17") (pintype "bidirectional"))
    )
    (net (code "131") (name "unconnected-(IC1B-PRTCTL5-Pad18)") (class "Default")
      (node (ref "IC1") (pin "18") (pinfunction "PRTCTL5_18") (pintype "bidirectional"))
    )
    (net (code "132") (name "unconnected-(IC1C-NFDX_LED-Pad20)") (class "Default")
      (node (ref "IC1") (pin "20") (pinfunction "NFDX_LED_20") (pintype "bidirectional"))
    )
    (net (code "133") (name "unconnected-(IC2-CBUS0-Pad15)") (class "Default")
      (node (ref "IC2") (pin "15") (pinfunction "CBUS0_15") (pintype "bidirectional"))
    )
    (net (code "134") (name "unconnected-(IC2-CBUS1-Pad14)") (class "Default")
      (node (ref "IC2") (pin "14") (pinfunction "CBUS1_14") (pintype "bidirectional"))
    )
    (net (code "135") (name "unconnected-(IC2-CBUS2-Pad7)") (class "Default")
      (node (ref "IC2") (pin "7") (pinfunction "CBUS2_7") (pintype "bidirectional"))
    )
    (net (code "136") (name "unconnected-(IC2-CBUS3-Pad16)") (class "Default")
      (node (ref "IC2") (pin "16") (pinfunction "CBUS3_16") (pintype "bidirectional"))
    )
    (net (code "137") (name "unconnected-(IC2-~{CTS}-Pad6)") (class "Default")
      (node (ref "IC2") (pin "6") (pinfunction "~{CTS}_6") (pintype "input"))
    )
    (net (code "138") (name "unconnected-(IC2-~{RTS}-Pad2)") (class "Default")
      (node (ref "IC2") (pin "2") (pinfunction "~{RTS}_2") (pintype "output"))
    )
    (net (code "139") (name "unconnected-(IC5A-DB2{slash}RTS-Pad18)") (class "Default")
      (node (ref "IC5") (pin "18") (pinfunction "DB2/RTS_18") (pintype "bidirectional"))
    )
    (net (code "140") (name "unconnected-(IC5A-DB3{slash}CTS-Pad19)") (class "Default")
      (node (ref "IC5") (pin "19") (pinfunction "DB3/CTS_19") (pintype "bidirectional"))
    )
    (net (code "141") (name "unconnected-(IC5A-DB4{slash}DTR-Pad21)") (class "Default")
      (node (ref "IC5") (pin "21") (pinfunction "DB4/DTR_21") (pintype "bidirectional"))
    )
    (net (code "142") (name "unconnected-(IC5A-DB5{slash}DSR-Pad22)") (class "Default")
      (node (ref "IC5") (pin "22") (pinfunction "DB5/DSR_22") (pintype "bidirectional"))
    )
    (net (code "143") (name "unconnected-(IC5A-DB6{slash}DCD-Pad23)") (class "Default")
      (node (ref "IC5") (pin "23") (pinfunction "DB6/DCD_23") (pintype "bidirectional"))
    )
    (net (code "144") (name "unconnected-(IC5A-DB7{slash}RI-Pad24)") (class "Default")
      (node (ref "IC5") (pin "24") (pinfunction "DB7/RI_24") (pintype "bidirectional"))
    )
    (net (code "145") (name "unconnected-(IC5B-DB2{slash}RTS-Pad28)") (class "Default")
      (node (ref "IC5") (pin "28") (pinfunction "DB2/RTS_28") (pintype "bidirectional"))
    )
    (net (code "146") (name "unconnected-(IC5B-DB3{slash}CTS-Pad29)") (class "Default")
      (node (ref "IC5") (pin "29") (pinfunction "DB3/CTS_29") (pintype "bidirectional"))
    )
    (net (code "147") (name "unconnected-(IC5B-DB5{slash}DSR-Pad32)") (class "Default")
      (node (ref "IC5") (pin "32") (pinfunction "DB5/DSR_32") (pintype "bidirectional"))
    )
    (net (code "148") (name "unconnected-(IC5B-DB6{slash}DCD-Pad33)") (class "Default")
      (node (ref "IC5") (pin "33") (pinfunction "DB6/DCD_33") (pintype "bidirectional"))
    )
    (net (code "149") (name "unconnected-(IC5B-DB7{slash}RI-Pad34)") (class "Default")
      (node (ref "IC5") (pin "34") (pinfunction "DB7/RI_34") (pintype "bidirectional"))
    )
    (net (code "150") (name "unconnected-(IC5C-DB2{slash}RTS-Pad40)") (class "Default")
      (node (ref "IC5") (pin "40") (pinfunction "DB2/RTS_40") (pintype "bidirectional"))
    )
    (net (code "151") (name "unconnected-(IC5C-DB3{slash}CTS-Pad41)") (class "Default")
      (node (ref "IC5") (pin "41") (pinfunction "DB3/CTS_41") (pintype "bidirectional"))
    )
    (net (code "152") (name "unconnected-(IC5C-DB4{slash}DTR-Pad43)") (class "Default")
      (node (ref "IC5") (pin "43") (pinfunction "DB4/DTR_43") (pintype "bidirectional"))
    )
    (net (code "153") (name "unconnected-(IC5C-DB5{slash}DSR-Pad44)") (class "Default")
      (node (ref "IC5") (pin "44") (pinfunction "DB5/DSR_44") (pintype "bidirectional"))
    )
    (net (code "154") (name "unconnected-(IC5C-DB6{slash}DCD-Pad45)") (class "Default")
      (node (ref "IC5") (pin "45") (pinfunction "DB6/DCD_45") (pintype "bidirectional"))
    )
    (net (code "155") (name "unconnected-(IC5C-DB7{slash}RI-Pad46)") (class "Default")
      (node (ref "IC5") (pin "46") (pinfunction "DB7/RI_46") (pintype "bidirectional"))
    )
    (net (code "156") (name "unconnected-(IC5D-EECLK-Pad62)") (class "Default")
      (node (ref "IC5") (pin "62") (pinfunction "EECLK_62") (pintype "output"))
    )
    (net (code "157") (name "unconnected-(IC5D-EECS-Pad63)") (class "Default")
      (node (ref "IC5") (pin "63") (pinfunction "EECS_63") (pintype "bidirectional"))
    )
    (net (code "158") (name "unconnected-(IC5D-PWREN#-Pad60)") (class "Default")
      (node (ref "IC5") (pin "60") (pinfunction "PWREN#_60") (pintype "output"))
    )
    (net (code "159") (name "unconnected-(IC5D-SUSPEND#-Pad36)") (class "Default")
      (node (ref "IC5") (pin "36") (pinfunction "SUSPEND#_36") (pintype "output"))
    )
    (net (code "160") (name "unconnected-(IC5E-DB2{slash}RTS-Pad53)") (class "Default")
      (node (ref "IC5") (pin "53") (pinfunction "DB2/RTS_53") (pintype "bidirectional"))
    )
    (net (code "161") (name "unconnected-(IC5E-DB3{slash}CTS-Pad54)") (class "Default")
      (node (ref "IC5") (pin "54") (pinfunction "DB3/CTS_54") (pintype "bidirectional"))
    )
    (net (code "162") (name "unconnected-(IC5E-DB4{slash}DTR-Pad55)") (class "Default")
      (node (ref "IC5") (pin "55") (pinfunction "DB4/DTR_55") (pintype "bidirectional"))
    )
    (net (code "163") (name "unconnected-(IC5E-DB5{slash}DSR-Pad57)") (class "Default")
      (node (ref "IC5") (pin "57") (pinfunction "DB5/DSR_57") (pintype "bidirectional"))
    )
    (net (code "164") (name "unconnected-(IC5E-DB6{slash}DCD-Pad58)") (class "Default")
      (node (ref "IC5") (pin "58") (pinfunction "DB6/DCD_58") (pintype "bidirectional"))
    )
    (net (code "165") (name "unconnected-(IC5E-DB7{slash}RI-Pad59)") (class "Default")
      (node (ref "IC5") (pin "59") (pinfunction "DB7/RI_59") (pintype "bidirectional"))
    )
    (net (code "166") (name "unconnected-(IC7-C_SENSE-Pad5)") (class "Default")
      (node (ref "IC7") (pin "5") (pinfunction "C_SENSE_5") (pintype "bidirectional"))
    )
    (net (code "167") (name "unconnected-(IC7-SEL-Pad4)") (class "Default")
      (node (ref "IC7") (pin "4") (pinfunction "SEL_4") (pintype "bidirectional"))
    )
    (net (code "168") (name "unconnected-(IC7-SEN-Pad2)") (class "Default")
      (node (ref "IC7") (pin "2") (pinfunction "SEN_2") (pintype "bidirectional"))
    )
    (net (code "169") (name "unconnected-(IC8-C_SENSE-Pad5)") (class "Default")
      (node (ref "IC8") (pin "5") (pinfunction "C_SENSE_5") (pintype "bidirectional"))
    )
    (net (code "170") (name "unconnected-(IC8-SEL-Pad4)") (class "Default")
      (node (ref "IC8") (pin "4") (pinfunction "SEL_4") (pintype "bidirectional"))
    )
    (net (code "171") (name "unconnected-(IC8-SEN-Pad2)") (class "Default")
      (node (ref "IC8") (pin "2") (pinfunction "SEN_2") (pintype "bidirectional"))
    )
  )
)
